# board2.net
KiCad netlist of a schematic drawn in EAGLE
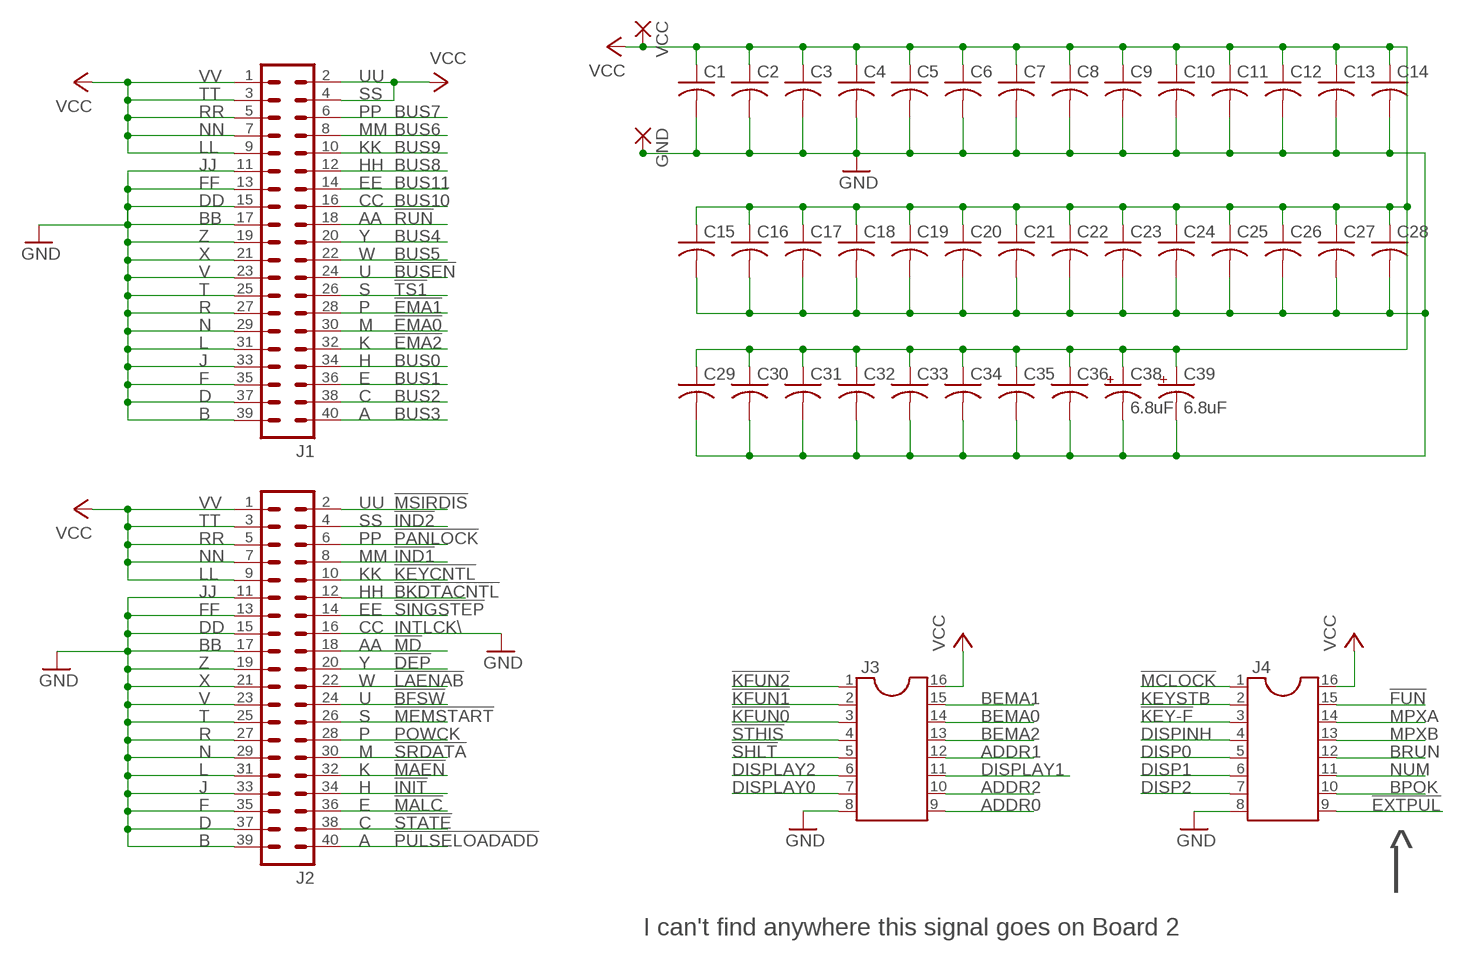
[diagram p0: schematic, sheet 1]
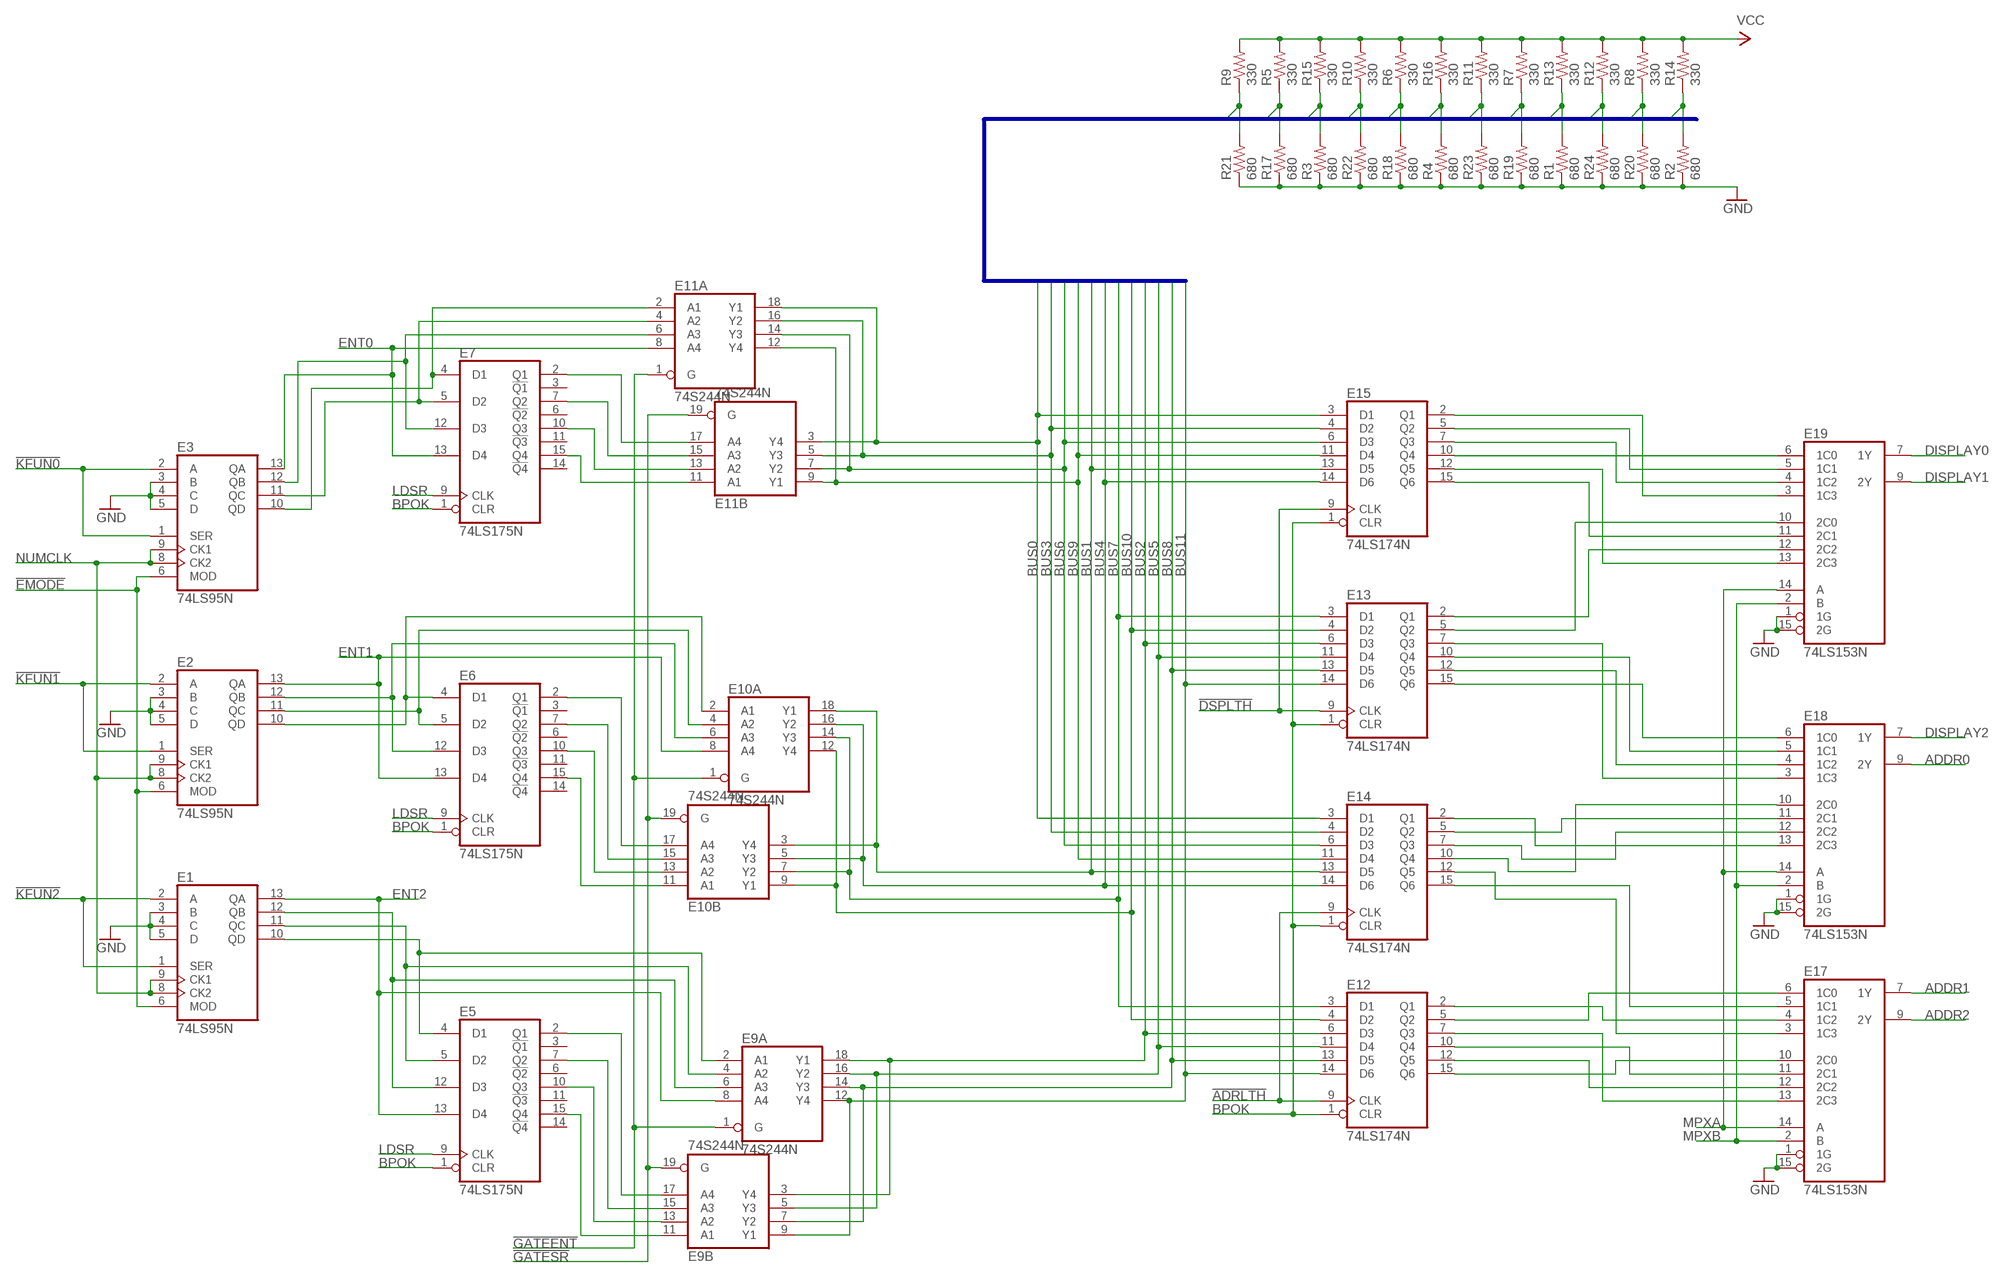
[diagram p1: schematic, sheet 2]
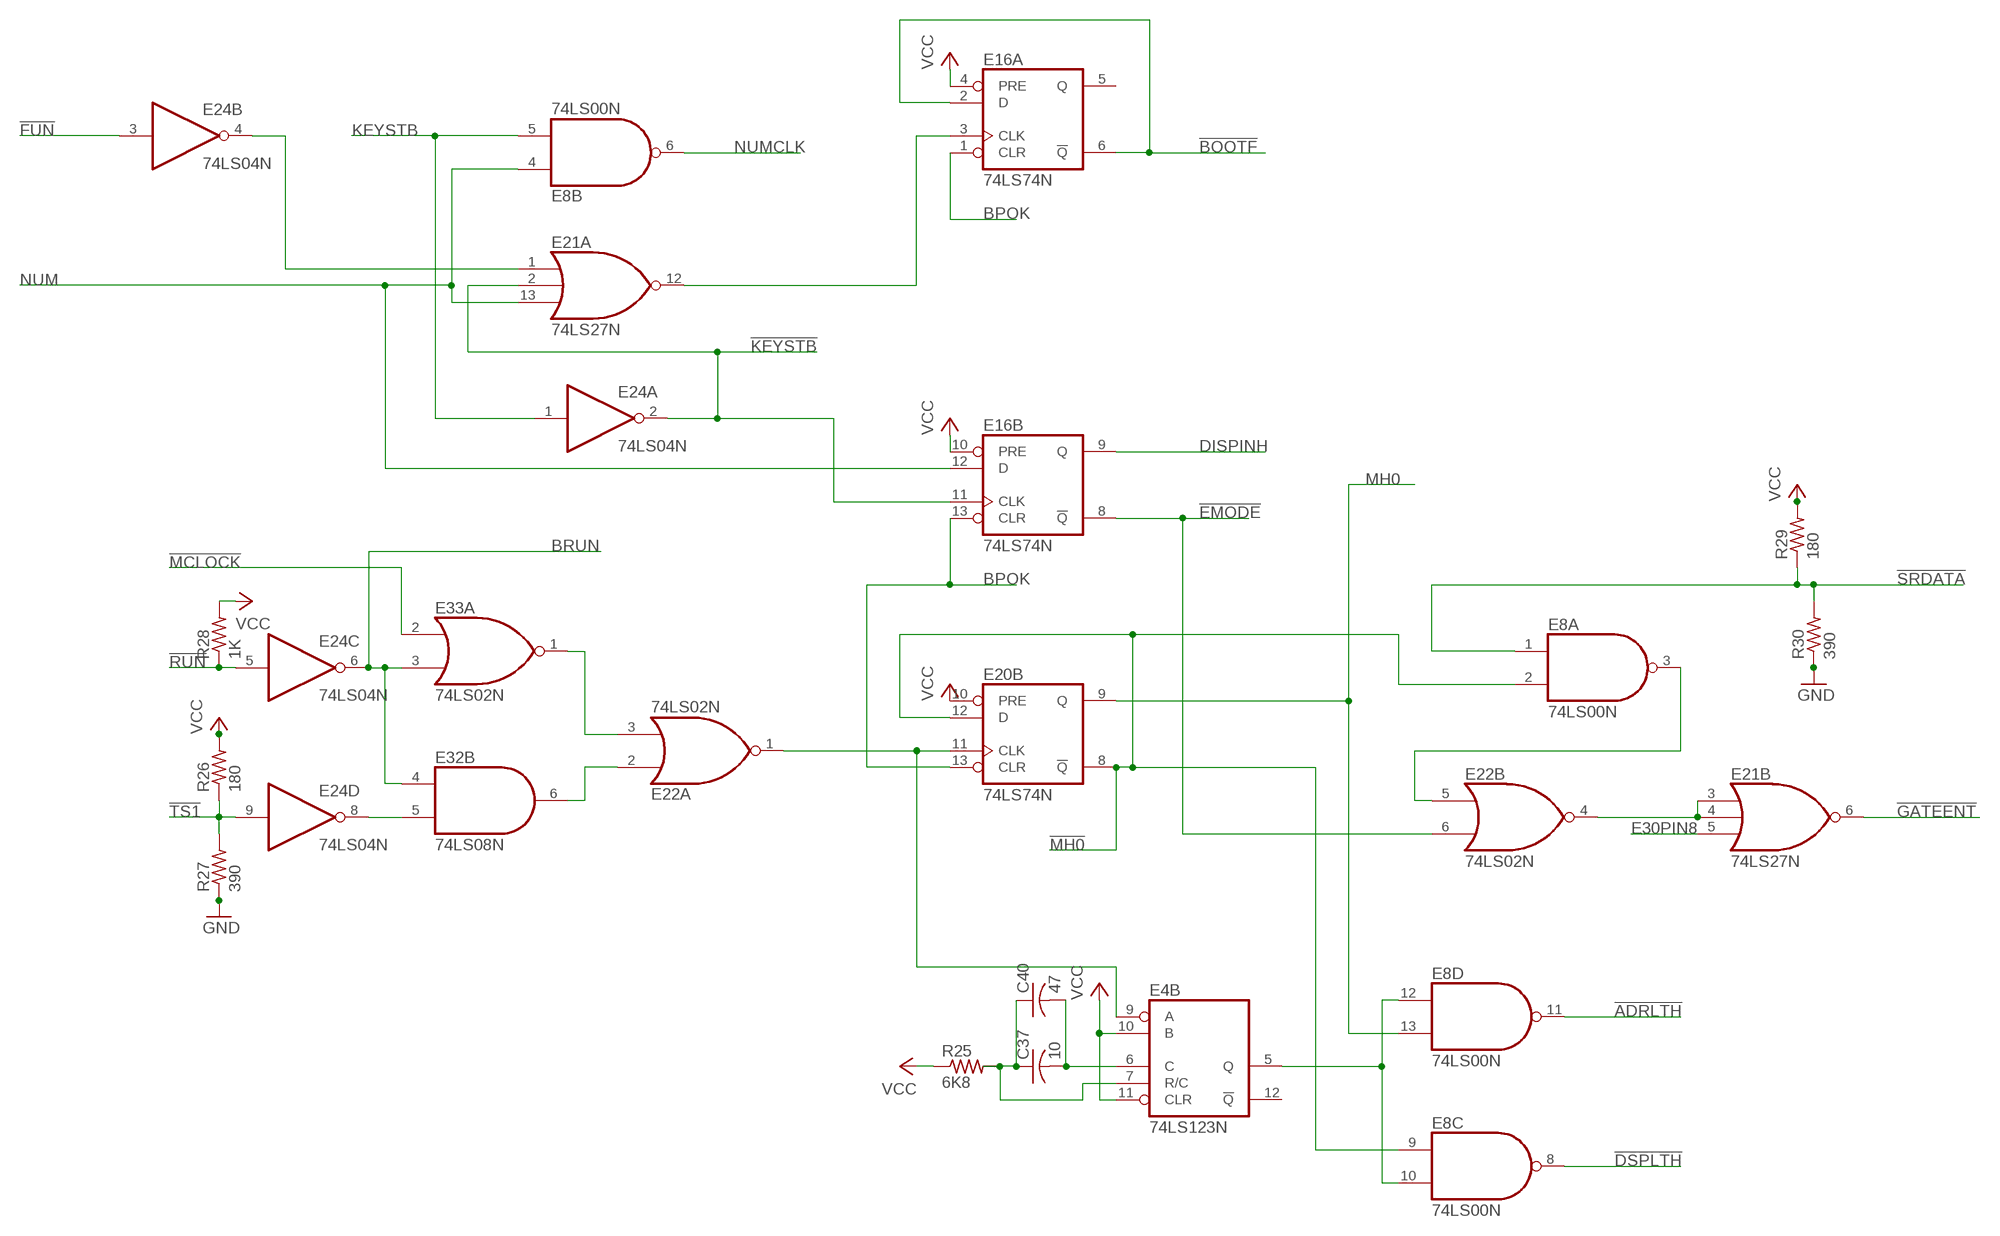
[diagram p2: schematic, sheet 3]
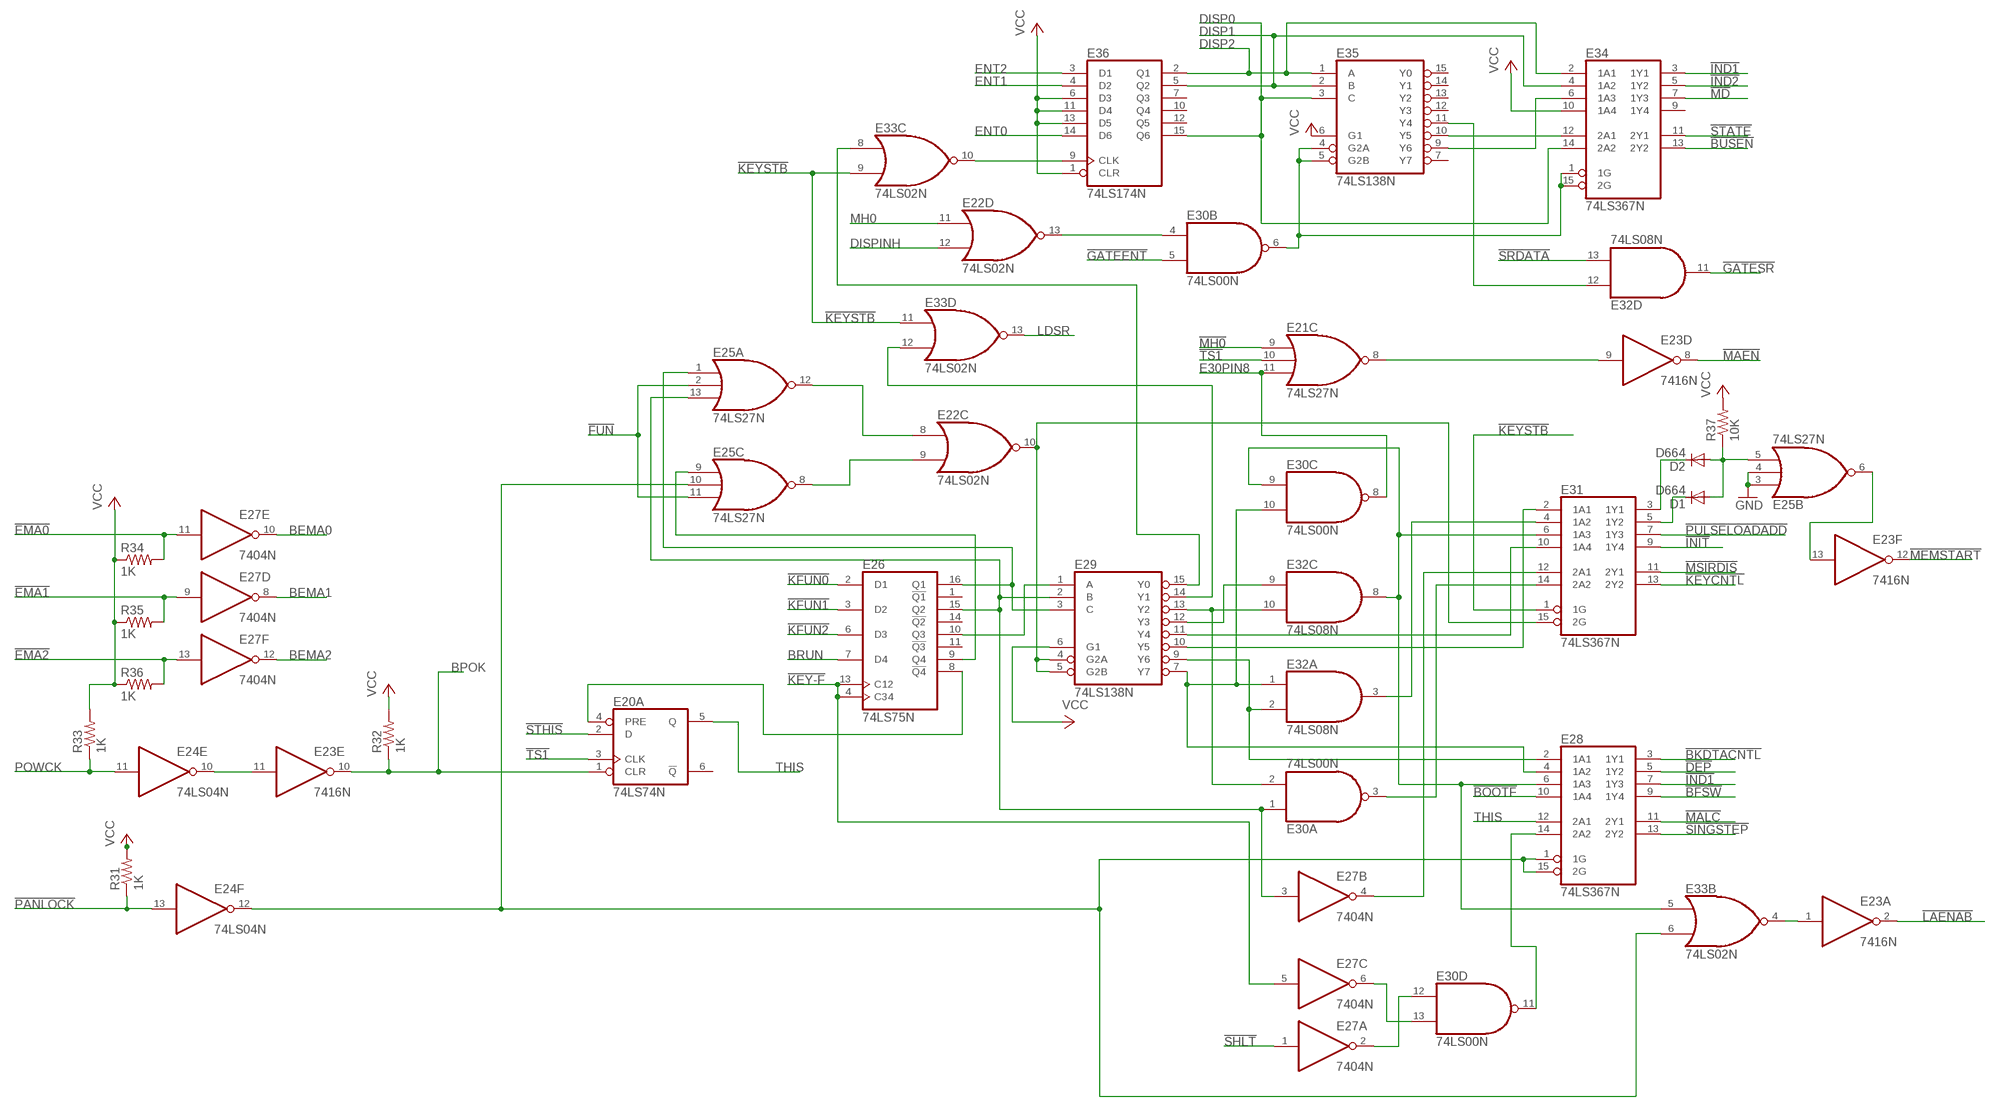
[diagram p3: schematic, sheet 4]

(export (version "E")
  (design (tool "Eeschema 10.0.6"))
  (components
    (comp (ref "C37")
      (value "10")
      (footprint "eagle-import:C050-025X075")
      (libsource (lib "eagle-import") (part "C-US050-025X075"))
    )
    (comp (ref "C40")
      (value "47")
      (footprint "eagle-import:C050-025X075")
      (libsource (lib "eagle-import") (part "C-US050-025X075"))
    )
    (comp (ref "E4")
      (value "74LS123N")
      (footprint "eagle-import:DIL16")
      (libsource (lib "eagle-import") (part "74123NLS"))
    )
    (comp (ref "E8")
      (value "74LS00N")
      (footprint "eagle-import:DIL14")
      (libsource (lib "eagle-import") (part "7400NLS"))
    )
    (comp (ref "E16")
      (value "74LS74N")
      (footprint "eagle-import:DIL14")
      (libsource (lib "eagle-import") (part "7474NLS"))
    )
    (comp (ref "E20")
      (value "74LS74N")
      (footprint "eagle-import:DIL14")
      (libsource (lib "eagle-import") (part "7474NLS"))
    )
    (comp (ref "E21")
      (value "74LS27N")
      (footprint "eagle-import:DIL14")
      (libsource (lib "eagle-import") (part "7427NLS"))
    )
    (comp (ref "E22")
      (value "74LS02N")
      (footprint "eagle-import:DIL14")
      (libsource (lib "eagle-import") (part "7402NLS"))
    )
    (comp (ref "E24")
      (value "74LS04N")
      (footprint "eagle-import:DIL14")
      (libsource (lib "eagle-import") (part "7404NLS"))
    )
    (comp (ref "E32")
      (value "74LS08N")
      (footprint "eagle-import:DIL14")
      (libsource (lib "eagle-import") (part "7408NLS"))
    )
    (comp (ref "E33")
      (value "74LS02N")
      (footprint "eagle-import:DIL14")
      (libsource (lib "eagle-import") (part "7402NLS"))
    )
    (comp (ref "R25")
      (value "6K8")
      (footprint "eagle-import:0207_10")
      (libsource (lib "eagle-import") (part "R-US_0207/10"))
    )
    (comp (ref "R26")
      (value "180")
      (footprint "eagle-import:0207_10")
      (libsource (lib "eagle-import") (part "R-US_0207/10"))
    )
    (comp (ref "R27")
      (value "390")
      (footprint "eagle-import:0207_10")
      (libsource (lib "eagle-import") (part "R-US_0207/10"))
    )
    (comp (ref "R28")
      (value "1K")
      (footprint "eagle-import:0207_10")
      (libsource (lib "eagle-import") (part "R-US_0207/10"))
    )
    (comp (ref "R29")
      (value "180")
      (footprint "eagle-import:0207_10")
      (libsource (lib "eagle-import") (part "R-US_0207/10"))
    )
    (comp (ref "R30")
      (value "390")
      (footprint "eagle-import:0207_10")
      (libsource (lib "eagle-import") (part "R-US_0207/10"))
    )
    (comp (ref "D1")
      (value "D664")
      (footprint "eagle-import:DO35-10")
      (libsource (lib "eagle-import") (part "1N4148DO35-10"))
    )
    (comp (ref "D2")
      (value "D664")
      (footprint "eagle-import:DO35-10")
      (libsource (lib "eagle-import") (part "1N4148DO35-10"))
    )
    (comp (ref "E23")
      (value "7416N")
      (footprint "eagle-import:DIL14")
      (libsource (lib "eagle-import") (part "7416N"))
    )
    (comp (ref "E25")
      (value "74LS27N")
      (footprint "eagle-import:DIL14")
      (libsource (lib "eagle-import") (part "7427NLS"))
    )
    (comp (ref "E26")
      (value "74LS75N")
      (footprint "eagle-import:DIL16")
      (libsource (lib "eagle-import") (part "7475NLS"))
    )
    (comp (ref "E27")
      (value "7404N")
      (footprint "eagle-import:DIL14")
      (libsource (lib "eagle-import") (part "7404N"))
    )
    (comp (ref "E28")
      (value "74LS367N")
      (footprint "eagle-import:DIL16")
      (libsource (lib "eagle-import") (part "74367N"))
    )
    (comp (ref "E29")
      (value "74LS138N")
      (footprint "eagle-import:DIL16")
      (libsource (lib "eagle-import") (part "74138NLS"))
    )
    (comp (ref "E30")
      (value "74LS00N")
      (footprint "eagle-import:DIL14")
      (libsource (lib "eagle-import") (part "7400NLS"))
    )
    (comp (ref "E31")
      (value "74LS367N")
      (footprint "eagle-import:DIL16")
      (libsource (lib "eagle-import") (part "74367N"))
    )
    (comp (ref "E34")
      (value "74LS367N")
      (footprint "eagle-import:DIL16")
      (libsource (lib "eagle-import") (part "74367N"))
    )
    (comp (ref "E35")
      (value "74LS138N")
      (footprint "eagle-import:DIL16")
      (libsource (lib "eagle-import") (part "74138NLS"))
    )
    (comp (ref "E36")
      (value "74LS174N")
      (footprint "eagle-import:DIL16")
      (libsource (lib "eagle-import") (part "74174NLS"))
    )
    (comp (ref "R31")
      (value "1K")
      (footprint "eagle-import:0207_10")
      (libsource (lib "eagle-import") (part "R-US_0207/10"))
    )
    (comp (ref "R32")
      (value "1K")
      (footprint "eagle-import:0207_10")
      (libsource (lib "eagle-import") (part "R-US_0207/10"))
    )
    (comp (ref "R33")
      (value "1K")
      (footprint "eagle-import:0207_10")
      (libsource (lib "eagle-import") (part "R-US_0207/10"))
    )
    (comp (ref "R34")
      (value "1K")
      (footprint "eagle-import:0207_10")
      (libsource (lib "eagle-import") (part "R-US_0207/10"))
    )
    (comp (ref "R35")
      (value "1K")
      (footprint "eagle-import:0207_10")
      (libsource (lib "eagle-import") (part "R-US_0207/10"))
    )
    (comp (ref "R36")
      (value "1K")
      (footprint "eagle-import:0207_10")
      (libsource (lib "eagle-import") (part "R-US_0207/10"))
    )
    (comp (ref "R37")
      (value "10K")
      (footprint "eagle-import:0207_10")
      (libsource (lib "eagle-import") (part "R-US_0207/10"))
    )
    (comp (ref "C1")
      (value "C-US050-025X075")
      (footprint "eagle-import:C050-025X075")
      (libsource (lib "eagle-import") (part "C-US050-025X075"))
    )
    (comp (ref "C2")
      (value "C-US050-025X075")
      (footprint "eagle-import:C050-025X075")
      (libsource (lib "eagle-import") (part "C-US050-025X075"))
    )
    (comp (ref "C3")
      (value "C-US050-025X075")
      (footprint "eagle-import:C050-025X075")
      (libsource (lib "eagle-import") (part "C-US050-025X075"))
    )
    (comp (ref "C4")
      (value "C-US050-025X075")
      (footprint "eagle-import:C050-025X075")
      (libsource (lib "eagle-import") (part "C-US050-025X075"))
    )
    (comp (ref "C5")
      (value "C-US050-025X075")
      (footprint "eagle-import:C050-025X075")
      (libsource (lib "eagle-import") (part "C-US050-025X075"))
    )
    (comp (ref "C6")
      (value "C-US050-025X075")
      (footprint "eagle-import:C050-025X075")
      (libsource (lib "eagle-import") (part "C-US050-025X075"))
    )
    (comp (ref "C7")
      (value "C-US050-025X075")
      (footprint "eagle-import:C050-025X075")
      (libsource (lib "eagle-import") (part "C-US050-025X075"))
    )
    (comp (ref "C8")
      (value "C-US050-025X075")
      (footprint "eagle-import:C050-025X075")
      (libsource (lib "eagle-import") (part "C-US050-025X075"))
    )
    (comp (ref "C9")
      (value "C-US050-025X075")
      (footprint "eagle-import:C050-025X075")
      (libsource (lib "eagle-import") (part "C-US050-025X075"))
    )
    (comp (ref "C10")
      (value "C-US050-025X075")
      (footprint "eagle-import:C050-025X075")
      (libsource (lib "eagle-import") (part "C-US050-025X075"))
    )
    (comp (ref "C11")
      (value "C-US050-025X075")
      (footprint "eagle-import:C050-025X075")
      (libsource (lib "eagle-import") (part "C-US050-025X075"))
    )
    (comp (ref "C12")
      (value "C-US050-025X075")
      (footprint "eagle-import:C050-025X075")
      (libsource (lib "eagle-import") (part "C-US050-025X075"))
    )
    (comp (ref "C13")
      (value "C-US050-025X075")
      (footprint "eagle-import:C050-025X075")
      (libsource (lib "eagle-import") (part "C-US050-025X075"))
    )
    (comp (ref "C14")
      (value "C-US050-025X075")
      (footprint "eagle-import:C050-025X075")
      (libsource (lib "eagle-import") (part "C-US050-025X075"))
    )
    (comp (ref "C15")
      (value "C-US050-025X075")
      (footprint "eagle-import:C050-025X075")
      (libsource (lib "eagle-import") (part "C-US050-025X075"))
    )
    (comp (ref "C16")
      (value "C-US050-025X075")
      (footprint "eagle-import:C050-025X075")
      (libsource (lib "eagle-import") (part "C-US050-025X075"))
    )
    (comp (ref "C17")
      (value "C-US050-025X075")
      (footprint "eagle-import:C050-025X075")
      (libsource (lib "eagle-import") (part "C-US050-025X075"))
    )
    (comp (ref "C18")
      (value "C-US050-025X075")
      (footprint "eagle-import:C050-025X075")
      (libsource (lib "eagle-import") (part "C-US050-025X075"))
    )
    (comp (ref "C19")
      (value "C-US050-025X075")
      (footprint "eagle-import:C050-025X075")
      (libsource (lib "eagle-import") (part "C-US050-025X075"))
    )
    (comp (ref "C20")
      (value "C-US050-025X075")
      (footprint "eagle-import:C050-025X075")
      (libsource (lib "eagle-import") (part "C-US050-025X075"))
    )
    (comp (ref "C21")
      (value "C-US050-025X075")
      (footprint "eagle-import:C050-025X075")
      (libsource (lib "eagle-import") (part "C-US050-025X075"))
    )
    (comp (ref "C22")
      (value "C-US050-025X075")
      (footprint "eagle-import:C050-025X075")
      (libsource (lib "eagle-import") (part "C-US050-025X075"))
    )
    (comp (ref "C23")
      (value "C-US050-025X075")
      (footprint "eagle-import:C050-025X075")
      (libsource (lib "eagle-import") (part "C-US050-025X075"))
    )
    (comp (ref "C24")
      (value "C-US050-025X075")
      (footprint "eagle-import:C050-025X075")
      (libsource (lib "eagle-import") (part "C-US050-025X075"))
    )
    (comp (ref "C25")
      (value "C-US050-025X075")
      (footprint "eagle-import:C050-025X075")
      (libsource (lib "eagle-import") (part "C-US050-025X075"))
    )
    (comp (ref "C26")
      (value "C-US050-025X075")
      (footprint "eagle-import:C050-025X075")
      (libsource (lib "eagle-import") (part "C-US050-025X075"))
    )
    (comp (ref "C27")
      (value "C-US050-025X075")
      (footprint "eagle-import:C050-025X075")
      (libsource (lib "eagle-import") (part "C-US050-025X075"))
    )
    (comp (ref "C28")
      (value "C-US050-025X075")
      (footprint "eagle-import:C050-025X075")
      (libsource (lib "eagle-import") (part "C-US050-025X075"))
    )
    (comp (ref "C29")
      (value "C-US050-025X075")
      (footprint "eagle-import:C050-025X075")
      (libsource (lib "eagle-import") (part "C-US050-025X075"))
    )
    (comp (ref "C30")
      (value "C-US050-025X075")
      (footprint "eagle-import:C050-025X075")
      (libsource (lib "eagle-import") (part "C-US050-025X075"))
    )
    (comp (ref "C31")
      (value "C-US050-025X075")
      (footprint "eagle-import:C050-025X075")
      (libsource (lib "eagle-import") (part "C-US050-025X075"))
    )
    (comp (ref "C32")
      (value "C-US050-025X075")
      (footprint "eagle-import:C050-025X075")
      (libsource (lib "eagle-import") (part "C-US050-025X075"))
    )
    (comp (ref "C33")
      (value "C-US050-025X075")
      (footprint "eagle-import:C050-025X075")
      (libsource (lib "eagle-import") (part "C-US050-025X075"))
    )
    (comp (ref "C34")
      (value "C-US050-025X075")
      (footprint "eagle-import:C050-025X075")
      (libsource (lib "eagle-import") (part "C-US050-025X075"))
    )
    (comp (ref "C35")
      (value "C-US050-025X075")
      (footprint "eagle-import:C050-025X075")
      (libsource (lib "eagle-import") (part "C-US050-025X075"))
    )
    (comp (ref "C36")
      (value "C-US050-025X075")
      (footprint "eagle-import:C050-025X075")
      (libsource (lib "eagle-import") (part "C-US050-025X075"))
    )
    (comp (ref "C38")
      (value "6.8uF")
      (footprint "eagle-import:E15-5")
      (libsource (lib "eagle-import") (part "CPOL-USE15-5AXIAL"))
    )
    (comp (ref "C39")
      (value "6.8uF")
      (footprint "eagle-import:E15-5")
      (libsource (lib "eagle-import") (part "CPOL-USE15-5AXIAL"))
    )
    (comp (ref "GND")
      (value "3,81/1,4")
      (footprint "eagle-import:3,81_1,4")
      (libsource (lib "eagle-import") (part "3,81/1,4"))
    )
    (comp (ref "J1")
      (value "40H")
      (footprint "eagle-import:40H")
      (libsource (lib "eagle-import") (part "40H"))
    )
    (comp (ref "J2")
      (value "40H")
      (footprint "eagle-import:40H")
      (libsource (lib "eagle-import") (part "40H"))
    )
    (comp (ref "J3")
      (value "DIL16S")
      (footprint "eagle-import:SOCKET-16")
      (libsource (lib "eagle-import") (part "DIL16S"))
    )
    (comp (ref "J4")
      (value "DIL16S")
      (footprint "eagle-import:SOCKET-16")
      (libsource (lib "eagle-import") (part "DIL16S"))
    )
    (comp (ref "VCC")
      (value "3,81/1,4")
      (footprint "eagle-import:3,81_1,4")
      (libsource (lib "eagle-import") (part "3,81/1,4"))
    )
    (comp (ref "E1")
      (value "74LS95N")
      (footprint "eagle-import:DIL14")
      (libsource (lib "eagle-import") (part "7495NLS"))
    )
    (comp (ref "E2")
      (value "74LS95N")
      (footprint "eagle-import:DIL14")
      (libsource (lib "eagle-import") (part "7495NLS"))
    )
    (comp (ref "E3")
      (value "74LS95N")
      (footprint "eagle-import:DIL14")
      (libsource (lib "eagle-import") (part "7495NLS"))
    )
    (comp (ref "E5")
      (value "74LS175N")
      (footprint "eagle-import:DIL16")
      (libsource (lib "eagle-import") (part "74175NLS"))
    )
    (comp (ref "E6")
      (value "74LS175N")
      (footprint "eagle-import:DIL16")
      (libsource (lib "eagle-import") (part "74175NLS"))
    )
    (comp (ref "E7")
      (value "74LS175N")
      (footprint "eagle-import:DIL16")
      (libsource (lib "eagle-import") (part "74175NLS"))
    )
    (comp (ref "E9")
      (value "74S244N")
      (footprint "eagle-import:DIL20")
      (libsource (lib "eagle-import") (part "74244NS"))
    )
    (comp (ref "E10")
      (value "74S244N")
      (footprint "eagle-import:DIL20")
      (libsource (lib "eagle-import") (part "74244NS"))
    )
    (comp (ref "E11")
      (value "74S244N")
      (footprint "eagle-import:DIL20")
      (libsource (lib "eagle-import") (part "74244NS"))
    )
    (comp (ref "E12")
      (value "74LS174N")
      (footprint "eagle-import:DIL16")
      (libsource (lib "eagle-import") (part "74174NLS"))
    )
    (comp (ref "E13")
      (value "74LS174N")
      (footprint "eagle-import:DIL16")
      (libsource (lib "eagle-import") (part "74174NLS"))
    )
    (comp (ref "E14")
      (value "74LS174N")
      (footprint "eagle-import:DIL16")
      (libsource (lib "eagle-import") (part "74174NLS"))
    )
    (comp (ref "E15")
      (value "74LS174N")
      (footprint "eagle-import:DIL16")
      (libsource (lib "eagle-import") (part "74174NLS"))
    )
    (comp (ref "E17")
      (value "74LS153N")
      (footprint "eagle-import:DIL16")
      (libsource (lib "eagle-import") (part "74153NLS"))
    )
    (comp (ref "E18")
      (value "74LS153N")
      (footprint "eagle-import:DIL16")
      (libsource (lib "eagle-import") (part "74153NLS"))
    )
    (comp (ref "E19")
      (value "74LS153N")
      (footprint "eagle-import:DIL16")
      (libsource (lib "eagle-import") (part "74153NLS"))
    )
    (comp (ref "R1")
      (value "680")
      (footprint "eagle-import:0207_10")
      (libsource (lib "eagle-import") (part "R-US_0207/10"))
    )
    (comp (ref "R2")
      (value "680")
      (footprint "eagle-import:0207_10")
      (libsource (lib "eagle-import") (part "R-US_0207/10"))
    )
    (comp (ref "R3")
      (value "680")
      (footprint "eagle-import:0207_10")
      (libsource (lib "eagle-import") (part "R-US_0207/10"))
    )
    (comp (ref "R4")
      (value "680")
      (footprint "eagle-import:0207_10")
      (libsource (lib "eagle-import") (part "R-US_0207/10"))
    )
    (comp (ref "R5")
      (value "330")
      (footprint "eagle-import:0207_10")
      (libsource (lib "eagle-import") (part "R-US_0207/10"))
    )
    (comp (ref "R6")
      (value "330")
      (footprint "eagle-import:0207_10")
      (libsource (lib "eagle-import") (part "R-US_0207/10"))
    )
    (comp (ref "R7")
      (value "330")
      (footprint "eagle-import:0207_10")
      (libsource (lib "eagle-import") (part "R-US_0207/10"))
    )
    (comp (ref "R8")
      (value "330")
      (footprint "eagle-import:0207_10")
      (libsource (lib "eagle-import") (part "R-US_0207/10"))
    )
    (comp (ref "R9")
      (value "330")
      (footprint "eagle-import:0207_10")
      (libsource (lib "eagle-import") (part "R-US_0207/10"))
    )
    (comp (ref "R10")
      (value "330")
      (footprint "eagle-import:0207_10")
      (libsource (lib "eagle-import") (part "R-US_0207/10"))
    )
    (comp (ref "R11")
      (value "330")
      (footprint "eagle-import:0207_10")
      (libsource (lib "eagle-import") (part "R-US_0207/10"))
    )
    (comp (ref "R12")
      (value "330")
      (footprint "eagle-import:0207_10")
      (libsource (lib "eagle-import") (part "R-US_0207/10"))
    )
    (comp (ref "R13")
      (value "330")
      (footprint "eagle-import:0207_10")
      (libsource (lib "eagle-import") (part "R-US_0207/10"))
    )
    (comp (ref "R14")
      (value "330")
      (footprint "eagle-import:0207_10")
      (libsource (lib "eagle-import") (part "R-US_0207/10"))
    )
    (comp (ref "R15")
      (value "330")
      (footprint "eagle-import:0207_10")
      (libsource (lib "eagle-import") (part "R-US_0207/10"))
    )
    (comp (ref "R16")
      (value "330")
      (footprint "eagle-import:0207_10")
      (libsource (lib "eagle-import") (part "R-US_0207/10"))
    )
    (comp (ref "R17")
      (value "680")
      (footprint "eagle-import:0207_10")
      (libsource (lib "eagle-import") (part "R-US_0207/10"))
    )
    (comp (ref "R18")
      (value "680")
      (footprint "eagle-import:0207_10")
      (libsource (lib "eagle-import") (part "R-US_0207/10"))
    )
    (comp (ref "R19")
      (value "680")
      (footprint "eagle-import:0207_10")
      (libsource (lib "eagle-import") (part "R-US_0207/10"))
    )
    (comp (ref "R20")
      (value "680")
      (footprint "eagle-import:0207_10")
      (libsource (lib "eagle-import") (part "R-US_0207/10"))
    )
    (comp (ref "R21")
      (value "680")
      (footprint "eagle-import:0207_10")
      (libsource (lib "eagle-import") (part "R-US_0207/10"))
    )
    (comp (ref "R22")
      (value "680")
      (footprint "eagle-import:0207_10")
      (libsource (lib "eagle-import") (part "R-US_0207/10"))
    )
    (comp (ref "R23")
      (value "680")
      (footprint "eagle-import:0207_10")
      (libsource (lib "eagle-import") (part "R-US_0207/10"))
    )
    (comp (ref "R24")
      (value "680")
      (footprint "eagle-import:0207_10")
      (libsource (lib "eagle-import") (part "R-US_0207/10"))
    )
  )
  (nets
    (net (code "1") (name "ADDR0") (class "Default")
      (node (ref "E18") (pin "9") (pinfunction "2Y_9") (pintype "output"))
      (node (ref "J3") (pin "9") (pinfunction "9_9") (pintype "passive"))
    )
    (net (code "2") (name "ADDR1") (class "Default")
      (node (ref "E17") (pin "7") (pinfunction "1Y_7") (pintype "output"))
      (node (ref "J3") (pin "12") (pinfunction "12_12") (pintype "passive"))
    )
    (net (code "3") (name "ADDR2") (class "Default")
      (node (ref "E17") (pin "9") (pinfunction "2Y_9") (pintype "output"))
      (node (ref "J3") (pin "10") (pinfunction "10_10") (pintype "passive"))
    )
    (net (code "4") (name "BEMA0") (class "Default")
      (node (ref "E27") (pin "10") (pinfunction "O_10") (pintype "output"))
      (node (ref "J3") (pin "14") (pinfunction "14_14") (pintype "passive"))
    )
    (net (code "5") (name "BEMA1") (class "Default")
      (node (ref "E27") (pin "8") (pinfunction "O_8") (pintype "output"))
      (node (ref "J3") (pin "15") (pinfunction "15_15") (pintype "passive"))
    )
    (net (code "6") (name "BEMA2") (class "Default")
      (node (ref "E27") (pin "12") (pinfunction "O_12") (pintype "output"))
      (node (ref "J3") (pin "13") (pinfunction "13_13") (pintype "passive"))
    )
    (net (code "7") (name "BPOK") (class "Default")
      (node (ref "E12") (pin "1") (pinfunction "CLR_1") (pintype "input"))
      (node (ref "E13") (pin "1") (pinfunction "CLR_1") (pintype "input"))
      (node (ref "E14") (pin "1") (pinfunction "CLR_1") (pintype "input"))
      (node (ref "E15") (pin "1") (pinfunction "CLR_1") (pintype "input"))
      (node (ref "E16") (pin "1") (pinfunction "CLR_1") (pintype "input"))
      (node (ref "E16") (pin "13") (pinfunction "CLR_13") (pintype "input"))
      (node (ref "E20") (pin "1") (pinfunction "CLR_1") (pintype "input"))
      (node (ref "E20") (pin "13") (pinfunction "CLR_13") (pintype "input"))
      (node (ref "E23") (pin "10") (pinfunction "O_10") (pintype "open_collector"))
      (node (ref "E5") (pin "1") (pinfunction "CLR_1") (pintype "input"))
      (node (ref "E6") (pin "1") (pinfunction "CLR_1") (pintype "input"))
      (node (ref "E7") (pin "1") (pinfunction "CLR_1") (pintype "input"))
      (node (ref "J4") (pin "10") (pinfunction "10_10") (pintype "passive"))
      (node (ref "R32") (pin "1") (pinfunction "1_1") (pintype "passive"))
    )
    (net (code "8") (name "BRUN") (class "Default")
      (node (ref "E24") (pin "6") (pinfunction "O_6") (pintype "output"))
      (node (ref "E26") (pin "7") (pinfunction "D4_7") (pintype "input"))
      (node (ref "E32") (pin "4") (pinfunction "I0_4") (pintype "input"))
      (node (ref "E33") (pin "3") (pinfunction "I1_3") (pintype "input"))
      (node (ref "J4") (pin "12") (pinfunction "12_12") (pintype "passive"))
    )
    (net (code "9") (name "BUS0") (class "Default")
      (node (ref "E11") (pin "18") (pinfunction "Y1_18") (pintype "tri_state"))
      (node (ref "E11") (pin "3") (pinfunction "Y4_3") (pintype "tri_state"))
      (node (ref "E14") (pin "3") (pinfunction "D1_3") (pintype "input"))
      (node (ref "E15") (pin "3") (pinfunction "D1_3") (pintype "input"))
      (node (ref "J1") (pin "34") (pinfunction "34_34") (pintype "passive"))
      (node (ref "R21") (pin "2") (pinfunction "2_2") (pintype "passive"))
      (node (ref "R9") (pin "1") (pinfunction "1_1") (pintype "passive"))
    )
    (net (code "10") (name "BUS1") (class "Default")
      (node (ref "E10") (pin "18") (pinfunction "Y1_18") (pintype "tri_state"))
      (node (ref "E10") (pin "3") (pinfunction "Y4_3") (pintype "tri_state"))
      (node (ref "E14") (pin "13") (pinfunction "D5_13") (pintype "input"))
      (node (ref "E15") (pin "13") (pinfunction "D5_13") (pintype "input"))
      (node (ref "J1") (pin "36") (pinfunction "36_36") (pintype "passive"))
      (node (ref "R17") (pin "2") (pinfunction "2_2") (pintype "passive"))
      (node (ref "R5") (pin "1") (pinfunction "1_1") (pintype "passive"))
    )
    (net (code "11") (name "BUS2") (class "Default")
      (node (ref "E12") (pin "6") (pinfunction "D3_6") (pintype "input"))
      (node (ref "E13") (pin "6") (pinfunction "D3_6") (pintype "input"))
      (node (ref "E9") (pin "18") (pinfunction "Y1_18") (pintype "tri_state"))
      (node (ref "E9") (pin "3") (pinfunction "Y4_3") (pintype "tri_state"))
      (node (ref "J1") (pin "38") (pinfunction "38_38") (pintype "passive"))
      (node (ref "R15") (pin "1") (pinfunction "1_1") (pintype "passive"))
      (node (ref "R3") (pin "2") (pinfunction "2_2") (pintype "passive"))
    )
    (net (code "12") (name "BUS3") (class "Default")
      (node (ref "E11") (pin "16") (pinfunction "Y2_16") (pintype "tri_state"))
      (node (ref "E11") (pin "5") (pinfunction "Y3_5") (pintype "tri_state"))
      (node (ref "E14") (pin "4") (pinfunction "D2_4") (pintype "input"))
      (node (ref "E15") (pin "4") (pinfunction "D2_4") (pintype "input"))
      (node (ref "J1") (pin "40") (pinfunction "40_40") (pintype "passive"))
      (node (ref "R10") (pin "1") (pinfunction "1_1") (pintype "passive"))
      (node (ref "R22") (pin "2") (pinfunction "2_2") (pintype "passive"))
    )
    (net (code "13") (name "BUS4") (class "Default")
      (node (ref "E10") (pin "16") (pinfunction "Y2_16") (pintype "tri_state"))
      (node (ref "E10") (pin "5") (pinfunction "Y3_5") (pintype "tri_state"))
      (node (ref "E14") (pin "14") (pinfunction "D6_14") (pintype "input"))
      (node (ref "E15") (pin "14") (pinfunction "D6_14") (pintype "input"))
      (node (ref "J1") (pin "20") (pinfunction "20_20") (pintype "passive"))
      (node (ref "R18") (pin "2") (pinfunction "2_2") (pintype "passive"))
      (node (ref "R6") (pin "1") (pinfunction "1_1") (pintype "passive"))
    )
    (net (code "14") (name "BUS5") (class "Default")
      (node (ref "E12") (pin "11") (pinfunction "D4_11") (pintype "input"))
      (node (ref "E13") (pin "11") (pinfunction "D4_11") (pintype "input"))
      (node (ref "E9") (pin "16") (pinfunction "Y2_16") (pintype "tri_state"))
      (node (ref "E9") (pin "5") (pinfunction "Y3_5") (pintype "tri_state"))
      (node (ref "J1") (pin "22") (pinfunction "22_22") (pintype "passive"))
      (node (ref "R16") (pin "1") (pinfunction "1_1") (pintype "passive"))
      (node (ref "R4") (pin "2") (pinfunction "2_2") (pintype "passive"))
    )
    (net (code "15") (name "BUS6") (class "Default")
      (node (ref "E11") (pin "14") (pinfunction "Y3_14") (pintype "tri_state"))
      (node (ref "E11") (pin "7") (pinfunction "Y2_7") (pintype "tri_state"))
      (node (ref "E14") (pin "6") (pinfunction "D3_6") (pintype "input"))
      (node (ref "E15") (pin "6") (pinfunction "D3_6") (pintype "input"))
      (node (ref "J1") (pin "8") (pinfunction "8_8") (pintype "passive"))
      (node (ref "R11") (pin "1") (pinfunction "1_1") (pintype "passive"))
      (node (ref "R23") (pin "2") (pinfunction "2_2") (pintype "passive"))
    )
    (net (code "16") (name "BUS7") (class "Default")
      (node (ref "E10") (pin "14") (pinfunction "Y3_14") (pintype "tri_state"))
      (node (ref "E10") (pin "7") (pinfunction "Y2_7") (pintype "tri_state"))
      (node (ref "E12") (pin "3") (pinfunction "D1_3") (pintype "input"))
      (node (ref "E13") (pin "3") (pinfunction "D1_3") (pintype "input"))
      (node (ref "J1") (pin "6") (pinfunction "6_6") (pintype "passive"))
      (node (ref "R19") (pin "2") (pinfunction "2_2") (pintype "passive"))
      (node (ref "R7") (pin "1") (pinfunction "1_1") (pintype "passive"))
    )
    (net (code "17") (name "BUS8") (class "Default")
      (node (ref "E12") (pin "13") (pinfunction "D5_13") (pintype "input"))
      (node (ref "E13") (pin "13") (pinfunction "D5_13") (pintype "input"))
      (node (ref "E9") (pin "14") (pinfunction "Y3_14") (pintype "tri_state"))
      (node (ref "E9") (pin "7") (pinfunction "Y2_7") (pintype "tri_state"))
      (node (ref "J1") (pin "12") (pinfunction "12_12") (pintype "passive"))
      (node (ref "R1") (pin "2") (pinfunction "2_2") (pintype "passive"))
      (node (ref "R13") (pin "1") (pinfunction "1_1") (pintype "passive"))
    )
    (net (code "18") (name "BUS9") (class "Default")
      (node (ref "E11") (pin "12") (pinfunction "Y4_12") (pintype "tri_state"))
      (node (ref "E11") (pin "9") (pinfunction "Y1_9") (pintype "tri_state"))
      (node (ref "E14") (pin "11") (pinfunction "D4_11") (pintype "input"))
      (node (ref "E15") (pin "11") (pinfunction "D4_11") (pintype "input"))
      (node (ref "J1") (pin "10") (pinfunction "10_10") (pintype "passive"))
      (node (ref "R12") (pin "1") (pinfunction "1_1") (pintype "passive"))
      (node (ref "R24") (pin "2") (pinfunction "2_2") (pintype "passive"))
    )
    (net (code "19") (name "BUS10") (class "Default")
      (node (ref "E10") (pin "12") (pinfunction "Y4_12") (pintype "tri_state"))
      (node (ref "E10") (pin "9") (pinfunction "Y1_9") (pintype "tri_state"))
      (node (ref "E12") (pin "4") (pinfunction "D2_4") (pintype "input"))
      (node (ref "E13") (pin "4") (pinfunction "D2_4") (pintype "input"))
      (node (ref "J1") (pin "16") (pinfunction "16_16") (pintype "passive"))
      (node (ref "R20") (pin "2") (pinfunction "2_2") (pintype "passive"))
      (node (ref "R8") (pin "1") (pinfunction "1_1") (pintype "passive"))
    )
    (net (code "20") (name "BUS11") (class "Default")
      (node (ref "E12") (pin "14") (pinfunction "D6_14") (pintype "input"))
      (node (ref "E13") (pin "14") (pinfunction "D6_14") (pintype "input"))
      (node (ref "E9") (pin "12") (pinfunction "Y4_12") (pintype "tri_state"))
      (node (ref "E9") (pin "9") (pinfunction "Y1_9") (pintype "tri_state"))
      (node (ref "J1") (pin "14") (pinfunction "14_14") (pintype "passive"))
      (node (ref "R14") (pin "1") (pinfunction "1_1") (pintype "passive"))
      (node (ref "R2") (pin "2") (pinfunction "2_2") (pintype "passive"))
    )
    (net (code "21") (name "DISP0") (class "Default")
      (node (ref "E34") (pin "14") (pinfunction "2A2_14") (pintype "input"))
      (node (ref "E35") (pin "3") (pinfunction "C_3") (pintype "input"))
      (node (ref "E36") (pin "15") (pinfunction "Q6_15") (pintype "output"))
      (node (ref "J4") (pin "5") (pinfunction "5_5") (pintype "passive"))
    )
    (net (code "22") (name "DISP1") (class "Default")
      (node (ref "E34") (pin "4") (pinfunction "1A2_4") (pintype "input"))
      (node (ref "E35") (pin "2") (pinfunction "B_2") (pintype "input"))
      (node (ref "E36") (pin "5") (pinfunction "Q2_5") (pintype "output"))
      (node (ref "J4") (pin "6") (pinfunction "6_6") (pintype "passive"))
    )
    (net (code "23") (name "DISP2") (class "Default")
      (node (ref "E34") (pin "2") (pinfunction "1A1_2") (pintype "input"))
      (node (ref "E35") (pin "1") (pinfunction "A_1") (pintype "input"))
      (node (ref "E36") (pin "2") (pinfunction "Q1_2") (pintype "output"))
      (node (ref "J4") (pin "7") (pinfunction "7_7") (pintype "passive"))
    )
    (net (code "24") (name "DISPINH") (class "Default")
      (node (ref "E16") (pin "9") (pinfunction "Q_9") (pintype "output"))
      (node (ref "E22") (pin "12") (pinfunction "I1_12") (pintype "input"))
      (node (ref "J4") (pin "4") (pinfunction "4_4") (pintype "passive"))
    )
    (net (code "25") (name "DISPLAY0") (class "Default")
      (node (ref "E19") (pin "7") (pinfunction "1Y_7") (pintype "output"))
      (node (ref "J3") (pin "7") (pinfunction "7_7") (pintype "passive"))
    )
    (net (code "26") (name "DISPLAY1") (class "Default")
      (node (ref "E19") (pin "9") (pinfunction "2Y_9") (pintype "output"))
      (node (ref "J3") (pin "11") (pinfunction "11_11") (pintype "passive"))
    )
    (net (code "27") (name "DISPLAY2") (class "Default")
      (node (ref "E18") (pin "7") (pinfunction "1Y_7") (pintype "output"))
      (node (ref "J3") (pin "6") (pinfunction "6_6") (pintype "passive"))
    )
    (net (code "28") (name "E30PIN8") (class "Default")
      (node (ref "E21") (pin "11") (pinfunction "I2_11") (pintype "input"))
      (node (ref "E21") (pin "5") (pinfunction "I2_5") (pintype "input"))
      (node (ref "E30") (pin "8") (pinfunction "O_8") (pintype "output"))
    )
    (net (code "29") (name "ENT0") (class "Default")
      (node (ref "E11") (pin "8") (pinfunction "A4_8") (pintype "input"))
      (node (ref "E3") (pin "13") (pinfunction "QA_13") (pintype "output"))
      (node (ref "E36") (pin "14") (pinfunction "D6_14") (pintype "input"))
      (node (ref "E7") (pin "13") (pinfunction "D4_13") (pintype "input"))
    )
    (net (code "30") (name "ENT1") (class "Default")
      (node (ref "E10") (pin "8") (pinfunction "A4_8") (pintype "input"))
      (node (ref "E2") (pin "13") (pinfunction "QA_13") (pintype "output"))
      (node (ref "E36") (pin "4") (pinfunction "D2_4") (pintype "input"))
      (node (ref "E6") (pin "13") (pinfunction "D4_13") (pintype "input"))
    )
    (net (code "31") (name "ENT2") (class "Default")
      (node (ref "E1") (pin "13") (pinfunction "QA_13") (pintype "output"))
      (node (ref "E36") (pin "3") (pinfunction "D1_3") (pintype "input"))
      (node (ref "E5") (pin "13") (pinfunction "D4_13") (pintype "input"))
      (node (ref "E9") (pin "8") (pinfunction "A4_8") (pintype "input"))
    )
    (net (code "32") (name "GND") (class "Default")
      (node (ref "C1") (pin "2") (pinfunction "2_2") (pintype "passive"))
      (node (ref "C10") (pin "2") (pinfunction "2_2") (pintype "passive"))
      (node (ref "C11") (pin "2") (pinfunction "2_2") (pintype "passive"))
      (node (ref "C12") (pin "2") (pinfunction "2_2") (pintype "passive"))
      (node (ref "C13") (pin "2") (pinfunction "2_2") (pintype "passive"))
      (node (ref "C14") (pin "2") (pinfunction "2_2") (pintype "passive"))
      (node (ref "C15") (pin "2") (pinfunction "2_2") (pintype "passive"))
      (node (ref "C16") (pin "2") (pinfunction "2_2") (pintype "passive"))
      (node (ref "C17") (pin "2") (pinfunction "2_2") (pintype "passive"))
      (node (ref "C18") (pin "2") (pinfunction "2_2") (pintype "passive"))
      (node (ref "C19") (pin "2") (pinfunction "2_2") (pintype "passive"))
      (node (ref "C2") (pin "2") (pinfunction "2_2") (pintype "passive"))
      (node (ref "C20") (pin "2") (pinfunction "2_2") (pintype "passive"))
      (node (ref "C21") (pin "2") (pinfunction "2_2") (pintype "passive"))
      (node (ref "C22") (pin "2") (pinfunction "2_2") (pintype "passive"))
      (node (ref "C23") (pin "2") (pinfunction "2_2") (pintype "passive"))
      (node (ref "C24") (pin "2") (pinfunction "2_2") (pintype "passive"))
      (node (ref "C25") (pin "2") (pinfunction "2_2") (pintype "passive"))
      (node (ref "C26") (pin "2") (pinfunction "2_2") (pintype "passive"))
      (node (ref "C27") (pin "2") (pinfunction "2_2") (pintype "passive"))
      (node (ref "C28") (pin "2") (pinfunction "2_2") (pintype "passive"))
      (node (ref "C29") (pin "2") (pinfunction "2_2") (pintype "passive"))
      (node (ref "C3") (pin "2") (pinfunction "2_2") (pintype "passive"))
      (node (ref "C30") (pin "2") (pinfunction "2_2") (pintype "passive"))
      (node (ref "C31") (pin "2") (pinfunction "2_2") (pintype "passive"))
      (node (ref "C32") (pin "2") (pinfunction "2_2") (pintype "passive"))
      (node (ref "C33") (pin "2") (pinfunction "2_2") (pintype "passive"))
      (node (ref "C34") (pin "2") (pinfunction "2_2") (pintype "passive"))
      (node (ref "C35") (pin "2") (pinfunction "2_2") (pintype "passive"))
      (node (ref "C36") (pin "2") (pinfunction "2_2") (pintype "passive"))
      (node (ref "C38") (pin "-") (pinfunction "-_-") (pintype "passive"))
      (node (ref "C39") (pin "-") (pinfunction "-_-") (pintype "passive"))
      (node (ref "C4") (pin "2") (pinfunction "2_2") (pintype "passive"))
      (node (ref "C5") (pin "2") (pinfunction "2_2") (pintype "passive"))
      (node (ref "C6") (pin "2") (pinfunction "2_2") (pintype "passive"))
      (node (ref "C7") (pin "2") (pinfunction "2_2") (pintype "passive"))
      (node (ref "C8") (pin "2") (pinfunction "2_2") (pintype "passive"))
      (node (ref "C9") (pin "2") (pinfunction "2_2") (pintype "passive"))
      (node (ref "E1") (pin "3") (pinfunction "B_3") (pintype "input"))
      (node (ref "E1") (pin "4") (pinfunction "C_4") (pintype "input"))
      (node (ref "E1") (pin "5") (pinfunction "D_5") (pintype "input"))
      (node (ref "E17") (pin "1") (pinfunction "1G_1") (pintype "input"))
      (node (ref "E17") (pin "15") (pinfunction "2G_15") (pintype "input"))
      (node (ref "E18") (pin "1") (pinfunction "1G_1") (pintype "input"))
      (node (ref "E18") (pin "15") (pinfunction "2G_15") (pintype "input"))
      (node (ref "E19") (pin "1") (pinfunction "1G_1") (pintype "input"))
      (node (ref "E19") (pin "15") (pinfunction "2G_15") (pintype "input"))
      (node (ref "E2") (pin "3") (pinfunction "B_3") (pintype "input"))
      (node (ref "E2") (pin "4") (pinfunction "C_4") (pintype "input"))
      (node (ref "E2") (pin "5") (pinfunction "D_5") (pintype "input"))
      (node (ref "E25") (pin "3") (pinfunction "I0_3") (pintype "input"))
      (node (ref "E25") (pin "4") (pinfunction "I1_4") (pintype "input"))
      (node (ref "E3") (pin "3") (pinfunction "B_3") (pintype "input"))
      (node (ref "E3") (pin "4") (pinfunction "C_4") (pintype "input"))
      (node (ref "E3") (pin "5") (pinfunction "D_5") (pintype "input"))
      (node (ref "GND") (pin "1") (pinfunction "P_1") (pintype "passive"))
      (node (ref "J1") (pin "11") (pinfunction "11_11") (pintype "passive"))
      (node (ref "J1") (pin "13") (pinfunction "13_13") (pintype "passive"))
      (node (ref "J1") (pin "15") (pinfunction "15_15") (pintype "passive"))
      (node (ref "J1") (pin "17") (pinfunction "17_17") (pintype "passive"))
      (node (ref "J1") (pin "19") (pinfunction "19_19") (pintype "passive"))
      (node (ref "J1") (pin "21") (pinfunction "21_21") (pintype "passive"))
      (node (ref "J1") (pin "23") (pinfunction "23_23") (pintype "passive"))
      (node (ref "J1") (pin "25") (pinfunction "25_25") (pintype "passive"))
      (node (ref "J1") (pin "27") (pinfunction "27_27") (pintype "passive"))
      (node (ref "J1") (pin "29") (pinfunction "29_29") (pintype "passive"))
      (node (ref "J1") (pin "31") (pinfunction "31_31") (pintype "passive"))
      (node (ref "J1") (pin "33") (pinfunction "33_33") (pintype "passive"))
      (node (ref "J1") (pin "35") (pinfunction "35_35") (pintype "passive"))
      (node (ref "J1") (pin "37") (pinfunction "37_37") (pintype "passive"))
      (node (ref "J1") (pin "39") (pinfunction "39_39") (pintype "passive"))
      (node (ref "J2") (pin "11") (pinfunction "11_11") (pintype "passive"))
      (node (ref "J2") (pin "13") (pinfunction "13_13") (pintype "passive"))
      (node (ref "J2") (pin "15") (pinfunction "15_15") (pintype "passive"))
      (node (ref "J2") (pin "16") (pinfunction "16_16") (pintype "passive"))
      (node (ref "J2") (pin "17") (pinfunction "17_17") (pintype "passive"))
      (node (ref "J2") (pin "19") (pinfunction "19_19") (pintype "passive"))
      (node (ref "J2") (pin "21") (pinfunction "21_21") (pintype "passive"))
      (node (ref "J2") (pin "23") (pinfunction "23_23") (pintype "passive"))
      (node (ref "J2") (pin "25") (pinfunction "25_25") (pintype "passive"))
      (node (ref "J2") (pin "27") (pinfunction "27_27") (pintype "passive"))
      (node (ref "J2") (pin "29") (pinfunction "29_29") (pintype "passive"))
      (node (ref "J2") (pin "31") (pinfunction "31_31") (pintype "passive"))
      (node (ref "J2") (pin "33") (pinfunction "33_33") (pintype "passive"))
      (node (ref "J2") (pin "35") (pinfunction "35_35") (pintype "passive"))
      (node (ref "J2") (pin "37") (pinfunction "37_37") (pintype "passive"))
      (node (ref "J2") (pin "39") (pinfunction "39_39") (pintype "passive"))
      (node (ref "J3") (pin "8") (pinfunction "8_8") (pintype "passive"))
      (node (ref "J4") (pin "8") (pinfunction "8_8") (pintype "passive"))
      (node (ref "R1") (pin "1") (pinfunction "1_1") (pintype "passive"))
      (node (ref "R17") (pin "1") (pinfunction "1_1") (pintype "passive"))
      (node (ref "R18") (pin "1") (pinfunction "1_1") (pintype "passive"))
      (node (ref "R19") (pin "1") (pinfunction "1_1") (pintype "passive"))
      (node (ref "R2") (pin "1") (pinfunction "1_1") (pintype "passive"))
      (node (ref "R20") (pin "1") (pinfunction "1_1") (pintype "passive"))
      (node (ref "R21") (pin "1") (pinfunction "1_1") (pintype "passive"))
      (node (ref "R22") (pin "1") (pinfunction "1_1") (pintype "passive"))
      (node (ref "R23") (pin "1") (pinfunction "1_1") (pintype "passive"))
      (node (ref "R24") (pin "1") (pinfunction "1_1") (pintype "passive"))
      (node (ref "R27") (pin "1") (pinfunction "1_1") (pintype "passive"))
      (node (ref "R3") (pin "1") (pinfunction "1_1") (pintype "passive"))
      (node (ref "R30") (pin "1") (pinfunction "1_1") (pintype "passive"))
      (node (ref "R4") (pin "1") (pinfunction "1_1") (pintype "passive"))
    )
    (net (code "33") (name "KEYSTB") (class "Default")
      (node (ref "E24") (pin "1") (pinfunction "I_1") (pintype "input"))
      (node (ref "E8") (pin "5") (pinfunction "I1_5") (pintype "input"))
      (node (ref "J4") (pin "2") (pinfunction "2_2") (pintype "passive"))
    )
    (net (code "34") (name "LDSR") (class "Default")
      (node (ref "E33") (pin "13") (pinfunction "O_13") (pintype "output"))
      (node (ref "E5") (pin "9") (pinfunction "CLK_9") (pintype "input"))
      (node (ref "E6") (pin "9") (pinfunction "CLK_9") (pintype "input"))
      (node (ref "E7") (pin "9") (pinfunction "CLK_9") (pintype "input"))
    )
    (net (code "35") (name "MH0") (class "Default")
      (node (ref "E20") (pin "9") (pinfunction "Q_9") (pintype "output"))
      (node (ref "E22") (pin "11") (pinfunction "I0_11") (pintype "input"))
      (node (ref "E8") (pin "13") (pinfunction "I1_13") (pintype "input"))
    )
    (net (code "36") (name "MPXA") (class "Default")
      (node (ref "E17") (pin "14") (pinfunction "A_14") (pintype "input"))
      (node (ref "E18") (pin "14") (pinfunction "A_14") (pintype "input"))
      (node (ref "E19") (pin "14") (pinfunction "A_14") (pintype "input"))
      (node (ref "J4") (pin "14") (pinfunction "14_14") (pintype "passive"))
    )
    (net (code "37") (name "MPXB") (class "Default")
      (node (ref "E17") (pin "2") (pinfunction "B_2") (pintype "input"))
      (node (ref "E18") (pin "2") (pinfunction "B_2") (pintype "input"))
      (node (ref "E19") (pin "2") (pinfunction "B_2") (pintype "input"))
      (node (ref "J4") (pin "13") (pinfunction "13_13") (pintype "passive"))
    )
    (net (code "38") (name "NUM") (class "Default")
      (node (ref "E16") (pin "12") (pinfunction "D_12") (pintype "input"))
      (node (ref "E21") (pin "13") (pinfunction "I2_13") (pintype "input"))
      (node (ref "E8") (pin "4") (pinfunction "I0_4") (pintype "input"))
      (node (ref "J4") (pin "11") (pinfunction "11_11") (pintype "passive"))
    )
    (net (code "39") (name "NUMCLK") (class "Default")
      (node (ref "E1") (pin "8") (pinfunction "CK2_8") (pintype "input"))
      (node (ref "E1") (pin "9") (pinfunction "CK1_9") (pintype "input"))
      (node (ref "E2") (pin "8") (pinfunction "CK2_8") (pintype "input"))
      (node (ref "E2") (pin "9") (pinfunction "CK1_9") (pintype "input"))
      (node (ref "E3") (pin "8") (pinfunction "CK2_8") (pintype "input"))
      (node (ref "E3") (pin "9") (pinfunction "CK1_9") (pintype "input"))
      (node (ref "E8") (pin "6") (pinfunction "O_6") (pintype "output"))
    )
    (net (code "40") (name "Net-(E1A-QB)") (class "Default")
      (node (ref "E1") (pin "12") (pinfunction "QB_12") (pintype "output"))
      (node (ref "E5") (pin "12") (pinfunction "D3_12") (pintype "input"))
      (node (ref "E9") (pin "6") (pinfunction "A3_6") (pintype "input"))
    )
    (net (code "41") (name "Net-(E1A-QC)") (class "Default")
      (node (ref "E1") (pin "11") (pinfunction "QC_11") (pintype "output"))
      (node (ref "E5") (pin "5") (pinfunction "D2_5") (pintype "input"))
      (node (ref "E9") (pin "4") (pinfunction "A2_4") (pintype "input"))
    )
    (net (code "42") (name "Net-(E1A-QD)") (class "Default")
      (node (ref "E1") (pin "10") (pinfunction "QD_10") (pintype "output"))
      (node (ref "E5") (pin "4") (pinfunction "D1_4") (pintype "input"))
      (node (ref "E9") (pin "2") (pinfunction "A1_2") (pintype "input"))
    )
    (net (code "43") (name "Net-(E4B-C)") (class "Default")
      (node (ref "C37") (pin "2") (pinfunction "2_2") (pintype "passive"))
      (node (ref "C40") (pin "2") (pinfunction "2_2") (pintype "passive"))
      (node (ref "E4") (pin "6") (pinfunction "C_6") (pintype "input"))
    )
    (net (code "44") (name "Net-(E4B-Q)") (class "Default")
      (node (ref "E4") (pin "5") (pinfunction "Q_5") (pintype "output"))
      (node (ref "E8") (pin "10") (pinfunction "I1_10") (pintype "input"))
      (node (ref "E8") (pin "12") (pinfunction "I0_12") (pintype "input"))
    )
    (net (code "45") (name "Net-(E4B-R{slash}C)") (class "Default")
      (node (ref "C37") (pin "1") (pinfunction "1_1") (pintype "passive"))
      (node (ref "C40") (pin "1") (pinfunction "1_1") (pintype "passive"))
      (node (ref "E4") (pin "7") (pinfunction "R/C_7") (pintype "input"))
      (node (ref "R25") (pin "2") (pinfunction "2_2") (pintype "passive"))
    )
    (net (code "46") (name "Net-(E5A-Q1)") (class "Default")
      (node (ref "E5") (pin "2") (pinfunction "Q1_2") (pintype "output"))
      (node (ref "E9") (pin "17") (pinfunction "A4_17") (pintype "input"))
    )
    (net (code "47") (name "Net-(E5A-Q2)") (class "Default")
      (node (ref "E5") (pin "7") (pinfunction "Q2_7") (pintype "output"))
      (node (ref "E9") (pin "15") (pinfunction "A3_15") (pintype "input"))
    )
    (net (code "48") (name "Net-(E5A-Q3)") (class "Default")
      (node (ref "E5") (pin "10") (pinfunction "Q3_10") (pintype "output"))
      (node (ref "E9") (pin "13") (pinfunction "A2_13") (pintype "input"))
    )
    (net (code "49") (name "Net-(E5A-Q4)") (class "Default")
      (node (ref "E5") (pin "15") (pinfunction "Q4_15") (pintype "output"))
      (node (ref "E9") (pin "11") (pinfunction "A1_11") (pintype "input"))
    )
    (net (code "50") (name "Net-(E10A-A1)") (class "Default")
      (node (ref "E10") (pin "2") (pinfunction "A1_2") (pintype "input"))
      (node (ref "E2") (pin "10") (pinfunction "QD_10") (pintype "output"))
      (node (ref "E6") (pin "4") (pinfunction "D1_4") (pintype "input"))
    )
    (net (code "51") (name "Net-(E10A-A2)") (class "Default")
      (node (ref "E10") (pin "4") (pinfunction "A2_4") (pintype "input"))
      (node (ref "E2") (pin "11") (pinfunction "QC_11") (pintype "output"))
      (node (ref "E6") (pin "5") (pinfunction "D2_5") (pintype "input"))
    )
    (net (code "52") (name "Net-(E10A-A3)") (class "Default")
      (node (ref "E10") (pin "6") (pinfunction "A3_6") (pintype "input"))
      (node (ref "E2") (pin "12") (pinfunction "QB_12") (pintype "output"))
      (node (ref "E6") (pin "12") (pinfunction "D3_12") (pintype "input"))
    )
    (net (code "53") (name "Net-(E10B-A1)") (class "Default")
      (node (ref "E10") (pin "11") (pinfunction "A1_11") (pintype "input"))
      (node (ref "E6") (pin "15") (pinfunction "Q4_15") (pintype "output"))
    )
    (net (code "54") (name "Net-(E10B-A2)") (class "Default")
      (node (ref "E10") (pin "13") (pinfunction "A2_13") (pintype "input"))
      (node (ref "E6") (pin "10") (pinfunction "Q3_10") (pintype "output"))
    )
    (net (code "55") (name "Net-(E10B-A3)") (class "Default")
      (node (ref "E10") (pin "15") (pinfunction "A3_15") (pintype "input"))
      (node (ref "E6") (pin "7") (pinfunction "Q2_7") (pintype "output"))
    )
    (net (code "56") (name "Net-(E10B-A4)") (class "Default")
      (node (ref "E10") (pin "17") (pinfunction "A4_17") (pintype "input"))
      (node (ref "E6") (pin "2") (pinfunction "Q1_2") (pintype "output"))
    )
    (net (code "57") (name "Net-(E11A-A1)") (class "Default")
      (node (ref "E11") (pin "2") (pinfunction "A1_2") (pintype "input"))
      (node (ref "E3") (pin "10") (pinfunction "QD_10") (pintype "output"))
      (node (ref "E7") (pin "4") (pinfunction "D1_4") (pintype "input"))
    )
    (net (code "58") (name "Net-(E11A-A2)") (class "Default")
      (node (ref "E11") (pin "4") (pinfunction "A2_4") (pintype "input"))
      (node (ref "E3") (pin "11") (pinfunction "QC_11") (pintype "output"))
      (node (ref "E7") (pin "5") (pinfunction "D2_5") (pintype "input"))
    )
    (net (code "59") (name "Net-(E11A-A3)") (class "Default")
      (node (ref "E11") (pin "6") (pinfunction "A3_6") (pintype "input"))
      (node (ref "E3") (pin "12") (pinfunction "QB_12") (pintype "output"))
      (node (ref "E7") (pin "12") (pinfunction "D3_12") (pintype "input"))
    )
    (net (code "60") (name "Net-(E11B-A1)") (class "Default")
      (node (ref "E11") (pin "11") (pinfunction "A1_11") (pintype "input"))
      (node (ref "E7") (pin "15") (pinfunction "Q4_15") (pintype "output"))
    )
    (net (code "61") (name "Net-(E11B-A2)") (class "Default")
      (node (ref "E11") (pin "13") (pinfunction "A2_13") (pintype "input"))
      (node (ref "E7") (pin "10") (pinfunction "Q3_10") (pintype "output"))
    )
    (net (code "62") (name "Net-(E11B-A3)") (class "Default")
      (node (ref "E11") (pin "15") (pinfunction "A3_15") (pintype "input"))
      (node (ref "E7") (pin "7") (pinfunction "Q2_7") (pintype "output"))
    )
    (net (code "63") (name "Net-(E11B-A4)") (class "Default")
      (node (ref "E11") (pin "17") (pinfunction "A4_17") (pintype "input"))
      (node (ref "E7") (pin "2") (pinfunction "Q1_2") (pintype "output"))
    )
    (net (code "64") (name "Net-(E12A-Q1)") (class "Default")
      (node (ref "E12") (pin "2") (pinfunction "Q1_2") (pintype "output"))
      (node (ref "E17") (pin "4") (pinfunction "1C2_4") (pintype "input"))
    )
    (net (code "65") (name "Net-(E12A-Q2)") (class "Default")
      (node (ref "E12") (pin "5") (pinfunction "Q2_5") (pintype "output"))
      (node (ref "E17") (pin "6") (pinfunction "1C0_6") (pintype "input"))
    )
    (net (code "66") (name "Net-(E12A-Q3)") (class "Default")
      (node (ref "E12") (pin "7") (pinfunction "Q3_7") (pintype "output"))
      (node (ref "E17") (pin "13") (pinfunction "2C3_13") (pintype "input"))
    )
    (net (code "67") (name "Net-(E12A-Q4)") (class "Default")
      (node (ref "E12") (pin "10") (pinfunction "Q4_10") (pintype "output"))
      (node (ref "E17") (pin "11") (pinfunction "2C1_11") (pintype "input"))
    )
    (net (code "68") (name "Net-(E12A-Q5)") (class "Default")
      (node (ref "E12") (pin "12") (pinfunction "Q5_12") (pintype "output"))
      (node (ref "E17") (pin "12") (pinfunction "2C2_12") (pintype "input"))
    )
    (net (code "69") (name "Net-(E12A-Q6)") (class "Default")
      (node (ref "E12") (pin "15") (pinfunction "Q6_15") (pintype "output"))
      (node (ref "E17") (pin "10") (pinfunction "2C0_10") (pintype "input"))
    )
    (net (code "70") (name "Net-(E13A-Q1)") (class "Default")
      (node (ref "E13") (pin "2") (pinfunction "Q1_2") (pintype "output"))
      (node (ref "E19") (pin "12") (pinfunction "2C2_12") (pintype "input"))
    )
    (net (code "71") (name "Net-(E13A-Q2)") (class "Default")
      (node (ref "E13") (pin "5") (pinfunction "Q2_5") (pintype "output"))
      (node (ref "E19") (pin "10") (pinfunction "2C0_10") (pintype "input"))
    )
    (net (code "72") (name "Net-(E13A-Q3)") (class "Default")
      (node (ref "E13") (pin "7") (pinfunction "Q3_7") (pintype "output"))
      (node (ref "E18") (pin "3") (pinfunction "1C3_3") (pintype "input"))
    )
    (net (code "73") (name "Net-(E13A-Q4)") (class "Default")
      (node (ref "E13") (pin "10") (pinfunction "Q4_10") (pintype "output"))
      (node (ref "E18") (pin "5") (pinfunction "1C1_5") (pintype "input"))
    )
    (net (code "74") (name "Net-(E13A-Q5)") (class "Default")
      (node (ref "E13") (pin "12") (pinfunction "Q5_12") (pintype "output"))
      (node (ref "E18") (pin "4") (pinfunction "1C2_4") (pintype "input"))
    )
    (net (code "75") (name "Net-(E13A-Q6)") (class "Default")
      (node (ref "E13") (pin "15") (pinfunction "Q6_15") (pintype "output"))
      (node (ref "E18") (pin "6") (pinfunction "1C0_6") (pintype "input"))
    )
    (net (code "76") (name "Net-(E14A-Q1)") (class "Default")
      (node (ref "E14") (pin "2") (pinfunction "Q1_2") (pintype "output"))
      (node (ref "E18") (pin "13") (pinfunction "2C3_13") (pintype "input"))
    )
    (net (code "77") (name "Net-(E14A-Q2)") (class "Default")
      (node (ref "E14") (pin "5") (pinfunction "Q2_5") (pintype "output"))
      (node (ref "E18") (pin "11") (pinfunction "2C1_11") (pintype "input"))
    )
    (net (code "78") (name "Net-(E14A-Q3)") (class "Default")
      (node (ref "E14") (pin "7") (pinfunction "Q3_7") (pintype "output"))
      (node (ref "E18") (pin "12") (pinfunction "2C2_12") (pintype "input"))
    )
    (net (code "79") (name "Net-(E14A-Q4)") (class "Default")
      (node (ref "E14") (pin "10") (pinfunction "Q4_10") (pintype "output"))
      (node (ref "E18") (pin "10") (pinfunction "2C0_10") (pintype "input"))
    )
    (net (code "80") (name "Net-(E14A-Q5)") (class "Default")
      (node (ref "E14") (pin "12") (pinfunction "Q5_12") (pintype "output"))
      (node (ref "E17") (pin "3") (pinfunction "1C3_3") (pintype "input"))
    )
    (net (code "81") (name "Net-(E14A-Q6)") (class "Default")
      (node (ref "E14") (pin "15") (pinfunction "Q6_15") (pintype "output"))
      (node (ref "E17") (pin "5") (pinfunction "1C1_5") (pintype "input"))
    )
    (net (code "82") (name "Net-(E15A-Q1)") (class "Default")
      (node (ref "E15") (pin "2") (pinfunction "Q1_2") (pintype "output"))
      (node (ref "E19") (pin "3") (pinfunction "1C3_3") (pintype "input"))
    )
    (net (code "83") (name "Net-(E15A-Q2)") (class "Default")
      (node (ref "E15") (pin "5") (pinfunction "Q2_5") (pintype "output"))
      (node (ref "E19") (pin "5") (pinfunction "1C1_5") (pintype "input"))
    )
    (net (code "84") (name "Net-(E15A-Q3)") (class "Default")
      (node (ref "E15") (pin "7") (pinfunction "Q3_7") (pintype "output"))
      (node (ref "E19") (pin "4") (pinfunction "1C2_4") (pintype "input"))
    )
    (net (code "85") (name "Net-(E15A-Q4)") (class "Default")
      (node (ref "E15") (pin "10") (pinfunction "Q4_10") (pintype "output"))
      (node (ref "E19") (pin "6") (pinfunction "1C0_6") (pintype "input"))
    )
    (net (code "86") (name "Net-(E15A-Q5)") (class "Default")
      (node (ref "E15") (pin "12") (pinfunction "Q5_12") (pintype "output"))
      (node (ref "E19") (pin "13") (pinfunction "2C3_13") (pintype "input"))
    )
    (net (code "87") (name "Net-(E15A-Q6)") (class "Default")
      (node (ref "E15") (pin "15") (pinfunction "Q6_15") (pintype "output"))
      (node (ref "E19") (pin "11") (pinfunction "2C1_11") (pintype "input"))
    )
    (net (code "88") (name "Net-(E16A-CLK)") (class "Default")
      (node (ref "E16") (pin "3") (pinfunction "CLK_3") (pintype "input"))
      (node (ref "E21") (pin "12") (pinfunction "O_12") (pintype "output"))
    )
    (net (code "89") (name "Net-(E20A-PRE)") (class "Default")
      (node (ref "E20") (pin "4") (pinfunction "PRE_4") (pintype "input"))
      (node (ref "E26") (pin "8") (pinfunction "~{Q4}_8") (pintype "output"))
    )
    (net (code "90") (name "Net-(E20B-CLK)") (class "Default")
      (node (ref "E20") (pin "11") (pinfunction "CLK_11") (pintype "input"))
      (node (ref "E22") (pin "1") (pinfunction "O_1") (pintype "output"))
      (node (ref "E4") (pin "9") (pinfunction "A_9") (pintype "input"))
    )
    (net (code "91") (name "Net-(E21A-I0)") (class "Default")
      (node (ref "E21") (pin "1") (pinfunction "I0_1") (pintype "input"))
      (node (ref "E24") (pin "4") (pinfunction "O_4") (pintype "output"))
    )
    (net (code "92") (name "Net-(E21B-I0)") (class "Default")
      (node (ref "E21") (pin "3") (pinfunction "I0_3") (pintype "input"))
      (node (ref "E21") (pin "4") (pinfunction "I1_4") (pintype "input"))
      (node (ref "E22") (pin "4") (pinfunction "O_4") (pintype "output"))
    )
    (net (code "93") (name "Net-(E21C-O)") (class "Default")
      (node (ref "E21") (pin "8") (pinfunction "O_8") (pintype "output"))
      (node (ref "E23") (pin "9") (pinfunction "I_9") (pintype "input"))
    )
    (net (code "94") (name "Net-(E22A-I0)") (class "Default")
      (node (ref "E22") (pin "2") (pinfunction "I0_2") (pintype "input"))
      (node (ref "E32") (pin "6") (pinfunction "O_6") (pintype "output"))
    )
    (net (code "95") (name "Net-(E22A-I1)") (class "Default")
      (node (ref "E22") (pin "3") (pinfunction "I1_3") (pintype "input"))
      (node (ref "E33") (pin "1") (pinfunction "O_1") (pintype "output"))
    )
    (net (code "96") (name "Net-(E22B-I0)") (class "Default")
      (node (ref "E22") (pin "5") (pinfunction "I0_5") (pintype "input"))
      (node (ref "E8") (pin "3") (pinfunction "O_3") (pintype "output"))
    )
    (net (code "97") (name "Net-(E22C-I0)") (class "Default")
      (node (ref "E22") (pin "8") (pinfunction "I0_8") (pintype "input"))
      (node (ref "E25") (pin "12") (pinfunction "O_12") (pintype "output"))
    )
    (net (code "98") (name "Net-(E22C-I1)") (class "Default")
      (node (ref "E22") (pin "9") (pinfunction "I1_9") (pintype "input"))
      (node (ref "E25") (pin "8") (pinfunction "O_8") (pintype "output"))
    )
    (net (code "99") (name "Net-(E22C-O)") (class "Default")
      (node (ref "E22") (pin "10") (pinfunction "O_10") (pintype "output"))
      (node (ref "E29") (pin "4") (pinfunction "G2A_4") (pintype "input"))
      (node (ref "E29") (pin "5") (pinfunction "G2B_5") (pintype "input"))
      (node (ref "E31") (pin "15") (pinfunction "2G_15") (pintype "input"))
    )
    (net (code "100") (name "Net-(E22D-O)") (class "Default")
      (node (ref "E22") (pin "13") (pinfunction "O_13") (pintype "output"))
      (node (ref "E30") (pin "4") (pinfunction "I0_4") (pintype "input"))
    )
    (net (code "101") (name "Net-(E23A-I)") (class "Default")
      (node (ref "E23") (pin "1") (pinfunction "I_1") (pintype "input"))
      (node (ref "E33") (pin "4") (pinfunction "O_4") (pintype "output"))
    )
    (net (code "102") (name "Net-(E23E-I)") (class "Default")
      (node (ref "E23") (pin "11") (pinfunction "I_11") (pintype "input"))
      (node (ref "E24") (pin "10") (pinfunction "O_10") (pintype "output"))
    )
    (net (code "103") (name "Net-(E23F-I)") (class "Default")
      (node (ref "E23") (pin "13") (pinfunction "I_13") (pintype "input"))
      (node (ref "E25") (pin "6") (pinfunction "O_6") (pintype "output"))
    )
    (net (code "104") (name "Net-(E24D-O)") (class "Default")
      (node (ref "E24") (pin "8") (pinfunction "O_8") (pintype "output"))
      (node (ref "E32") (pin "5") (pinfunction "I1_5") (pintype "input"))
    )
    (net (code "105") (name "Net-(E24F-O)") (class "Default")
      (node (ref "E24") (pin "12") (pinfunction "O_12") (pintype "output"))
      (node (ref "E25") (pin "10") (pinfunction "I1_10") (pintype "input"))
      (node (ref "E28") (pin "1") (pinfunction "1G_1") (pintype "input"))
      (node (ref "E28") (pin "15") (pinfunction "2G_15") (pintype "input"))
      (node (ref "E33") (pin "6") (pinfunction "I1_6") (pintype "input"))
    )
    (net (code "106") (name "Net-(E25A-I0)") (class "Default")
      (node (ref "E25") (pin "1") (pinfunction "I0_1") (pintype "input"))
      (node (ref "E26") (pin "16") (pinfunction "Q1_16") (pintype "output"))
      (node (ref "E29") (pin "3") (pinfunction "C_3") (pintype "input"))
    )
    (net (code "107") (name "Net-(E25A-I2)") (class "Default")
      (node (ref "E25") (pin "13") (pinfunction "I2_13") (pintype "input"))
      (node (ref "E26") (pin "15") (pinfunction "Q2_15") (pintype "output"))
      (node (ref "E27") (pin "3") (pinfunction "I_3") (pintype "input"))
      (node (ref "E29") (pin "2") (pinfunction "B_2") (pintype "input"))
      (node (ref "E30") (pin "1") (pinfunction "I0_1") (pintype "input"))
    )
    (net (code "108") (name "Net-(E25B-I2)") (class "Default")
      (node (ref "D1") (pin "A") (pinfunction "A_A") (pintype "passive"))
      (node (ref "D2") (pin "A") (pinfunction "A_A") (pintype "passive"))
      (node (ref "E25") (pin "5") (pinfunction "I2_5") (pintype "input"))
      (node (ref "R37") (pin "1") (pinfunction "1_1") (pintype "passive"))
    )
    (net (code "109") (name "Net-(E25C-I0)") (class "Default")
      (node (ref "E25") (pin "9") (pinfunction "I0_9") (pintype "input"))
      (node (ref "E26") (pin "9") (pinfunction "Q4_9") (pintype "output"))
    )
    (net (code "110") (name "Net-(E26A-Q3)") (class "Default")
      (node (ref "E26") (pin "10") (pinfunction "Q3_10") (pintype "output"))
      (node (ref "E29") (pin "1") (pinfunction "A_1") (pintype "input"))
    )
    (net (code "111") (name "Net-(E27A-O)") (class "Default")
      (node (ref "E27") (pin "2") (pinfunction "O_2") (pintype "output"))
      (node (ref "E30") (pin "12") (pinfunction "I0_12") (pintype "input"))
    )
    (net (code "112") (name "Net-(E27B-O)") (class "Default")
      (node (ref "E27") (pin "4") (pinfunction "O_4") (pintype "output"))
      (node (ref "E31") (pin "12") (pinfunction "2A1_12") (pintype "input"))
    )
    (net (code "113") (name "Net-(E27C-O)") (class "Default")
      (node (ref "E27") (pin "6") (pinfunction "O_6") (pintype "output"))
      (node (ref "E30") (pin "13") (pinfunction "I1_13") (pintype "input"))
    )
    (net (code "114") (name "Net-(E28A-1A1)") (class "Default")
      (node (ref "E28") (pin "2") (pinfunction "1A1_2") (pintype "input"))
      (node (ref "E29") (pin "9") (pinfunction "Y6_9") (pintype "output"))
      (node (ref "E32") (pin "2") (pinfunction "I1_2") (pintype "input"))
    )
    (net (code "115") (name "Net-(E28A-1A2)") (class "Default")
      (node (ref "E28") (pin "4") (pinfunction "1A2_4") (pintype "input"))
      (node (ref "E29") (pin "7") (pinfunction "Y7_7") (pintype "output"))
      (node (ref "E30") (pin "10") (pinfunction "I1_10") (pintype "input"))
      (node (ref "E32") (pin "1") (pinfunction "I0_1") (pintype "input"))
    )
    (net (code "116") (name "Net-(E28A-1A3)") (class "Default")
      (node (ref "E28") (pin "6") (pinfunction "1A3_6") (pintype "input"))
      (node (ref "E30") (pin "9") (pinfunction "I0_9") (pintype "input"))
      (node (ref "E31") (pin "6") (pinfunction "1A3_6") (pintype "input"))
      (node (ref "E32") (pin "8") (pinfunction "O_8") (pintype "output"))
      (node (ref "E33") (pin "5") (pinfunction "I0_5") (pintype "input"))
    )
    (net (code "117") (name "Net-(E28A-2A2)") (class "Default")
      (node (ref "E28") (pin "14") (pinfunction "2A2_14") (pintype "input"))
      (node (ref "E30") (pin "11") (pinfunction "O_11") (pintype "output"))
    )
    (net (code "118") (name "Net-(E29A-Y0)") (class "Default")
      (node (ref "E29") (pin "15") (pinfunction "Y0_15") (pintype "output"))
      (node (ref "E33") (pin "8") (pinfunction "I0_8") (pintype "input"))
    )
    (net (code "119") (name "Net-(E29A-Y1)") (class "Default")
      (node (ref "E29") (pin "14") (pinfunction "Y1_14") (pintype "output"))
      (node (ref "E33") (pin "12") (pinfunction "I1_12") (pintype "input"))
    )
    (net (code "120") (name "Net-(E29A-Y2)") (class "Default")
      (node (ref "E29") (pin "13") (pinfunction "Y2_13") (pintype "output"))
      (node (ref "E30") (pin "2") (pinfunction "I1_2") (pintype "input"))
      (node (ref "E32") (pin "10") (pinfunction "I1_10") (pintype "input"))
    )
    (net (code "121") (name "Net-(E29A-Y3)") (class "Default")
      (node (ref "E29") (pin "12") (pinfunction "Y3_12") (pintype "output"))
      (node (ref "E32") (pin "9") (pinfunction "I0_9") (pintype "input"))
    )
    (net (code "122") (name "Net-(E29A-Y4)") (class "Default")
      (node (ref "E29") (pin "11") (pinfunction "Y4_11") (pintype "output"))
      (node (ref "E31") (pin "10") (pinfunction "1A4_10") (pintype "input"))
    )
    (net (code "123") (name "Net-(E29A-Y5)") (class "Default")
      (node (ref "E29") (pin "10") (pinfunction "Y5_10") (pintype "output"))
      (node (ref "E31") (pin "2") (pinfunction "1A1_2") (pintype "input"))
    )
    (net (code "124") (name "Net-(E30A-O)") (class "Default")
      (node (ref "E30") (pin "3") (pinfunction "O_3") (pintype "output"))
      (node (ref "E31") (pin "14") (pinfunction "2A2_14") (pintype "input"))
    )
    (net (code "125") (name "Net-(E30B-O)") (class "Default")
      (node (ref "E30") (pin "6") (pinfunction "O_6") (pintype "output"))
      (node (ref "E34") (pin "1") (pinfunction "1G_1") (pintype "input"))
      (node (ref "E34") (pin "15") (pinfunction "2G_15") (pintype "input"))
      (node (ref "E35") (pin "4") (pinfunction "G2A_4") (pintype "input"))
      (node (ref "E35") (pin "5") (pinfunction "G2B_5") (pintype "input"))
    )
    (net (code "126") (name "Net-(E31A-1A2)") (class "Default")
      (node (ref "E31") (pin "4") (pinfunction "1A2_4") (pintype "input"))
      (node (ref "E32") (pin "3") (pinfunction "O_3") (pintype "output"))
    )
    (net (code "127") (name "Net-(E31A-1Y1)") (class "Default")
      (node (ref "D2") (pin "C") (pinfunction "C_C") (pintype "passive"))
      (node (ref "E31") (pin "3") (pinfunction "1Y1_3") (pintype "tri_state"))
    )
    (net (code "128") (name "Net-(E31A-1Y2)") (class "Default")
      (node (ref "D1") (pin "C") (pinfunction "C_C") (pintype "passive"))
      (node (ref "E31") (pin "5") (pinfunction "1Y2_5") (pintype "tri_state"))
    )
    (net (code "129") (name "Net-(E32D-I0)") (class "Default")
      (node (ref "E32") (pin "12") (pinfunction "I0_12") (pintype "input"))
      (node (ref "E35") (pin "11") (pinfunction "Y4_11") (pintype "output"))
    )
    (net (code "130") (name "Net-(E33C-O)") (class "Default")
      (node (ref "E33") (pin "10") (pinfunction "O_10") (pintype "output"))
      (node (ref "E36") (pin "9") (pinfunction "CLK_9") (pintype "input"))
    )
    (net (code "131") (name "Net-(E34A-1A3)") (class "Default")
      (node (ref "E34") (pin "6") (pinfunction "1A3_6") (pintype "input"))
      (node (ref "E35") (pin "9") (pinfunction "Y6_9") (pintype "output"))
    )
    (net (code "132") (name "Net-(E34A-2A1)") (class "Default")
      (node (ref "E34") (pin "12") (pinfunction "2A1_12") (pintype "input"))
      (node (ref "E35") (pin "10") (pinfunction "Y5_10") (pintype "output"))
    )
    (net (code "133") (name "POWCK") (class "Default")
      (node (ref "E24") (pin "11") (pinfunction "I_11") (pintype "input"))
      (node (ref "J2") (pin "28") (pinfunction "28_28") (pintype "passive"))
      (node (ref "R33") (pin "1") (pinfunction "1_1") (pintype "passive"))
    )
    (net (code "134") (name "THIS") (class "Default")
      (node (ref "E20") (pin "5") (pinfunction "Q_5") (pintype "output"))
      (node (ref "E28") (pin "12") (pinfunction "2A1_12") (pintype "input"))
    )
    (net (code "135") (name "VCC") (class "Default")
      (node (ref "C1") (pin "1") (pinfunction "1_1") (pintype "passive"))
      (node (ref "C10") (pin "1") (pinfunction "1_1") (pintype "passive"))
      (node (ref "C11") (pin "1") (pinfunction "1_1") (pintype "passive"))
      (node (ref "C12") (pin "1") (pinfunction "1_1") (pintype "passive"))
      (node (ref "C13") (pin "1") (pinfunction "1_1") (pintype "passive"))
      (node (ref "C14") (pin "1") (pinfunction "1_1") (pintype "passive"))
      (node (ref "C15") (pin "1") (pinfunction "1_1") (pintype "passive"))
      (node (ref "C16") (pin "1") (pinfunction "1_1") (pintype "passive"))
      (node (ref "C17") (pin "1") (pinfunction "1_1") (pintype "passive"))
      (node (ref "C18") (pin "1") (pinfunction "1_1") (pintype "passive"))
      (node (ref "C19") (pin "1") (pinfunction "1_1") (pintype "passive"))
      (node (ref "C2") (pin "1") (pinfunction "1_1") (pintype "passive"))
      (node (ref "C20") (pin "1") (pinfunction "1_1") (pintype "passive"))
      (node (ref "C21") (pin "1") (pinfunction "1_1") (pintype "passive"))
      (node (ref "C22") (pin "1") (pinfunction "1_1") (pintype "passive"))
      (node (ref "C23") (pin "1") (pinfunction "1_1") (pintype "passive"))
      (node (ref "C24") (pin "1") (pinfunction "1_1") (pintype "passive"))
      (node (ref "C25") (pin "1") (pinfunction "1_1") (pintype "passive"))
      (node (ref "C26") (pin "1") (pinfunction "1_1") (pintype "passive"))
      (node (ref "C27") (pin "1") (pinfunction "1_1") (pintype "passive"))
      (node (ref "C28") (pin "1") (pinfunction "1_1") (pintype "passive"))
      (node (ref "C29") (pin "1") (pinfunction "1_1") (pintype "passive"))
      (node (ref "C3") (pin "1") (pinfunction "1_1") (pintype "passive"))
      (node (ref "C30") (pin "1") (pinfunction "1_1") (pintype "passive"))
      (node (ref "C31") (pin "1") (pinfunction "1_1") (pintype "passive"))
      (node (ref "C32") (pin "1") (pinfunction "1_1") (pintype "passive"))
      (node (ref "C33") (pin "1") (pinfunction "1_1") (pintype "passive"))
      (node (ref "C34") (pin "1") (pinfunction "1_1") (pintype "passive"))
      (node (ref "C35") (pin "1") (pinfunction "1_1") (pintype "passive"))
      (node (ref "C36") (pin "1") (pinfunction "1_1") (pintype "passive"))
      (node (ref "C38") (pin "+") (pinfunction "+_+") (pintype "passive"))
      (node (ref "C39") (pin "+") (pinfunction "+_+") (pintype "passive"))
      (node (ref "C4") (pin "1") (pinfunction "1_1") (pintype "passive"))
      (node (ref "C5") (pin "1") (pinfunction "1_1") (pintype "passive"))
      (node (ref "C6") (pin "1") (pinfunction "1_1") (pintype "passive"))
      (node (ref "C7") (pin "1") (pinfunction "1_1") (pintype "passive"))
      (node (ref "C8") (pin "1") (pinfunction "1_1") (pintype "passive"))
      (node (ref "C9") (pin "1") (pinfunction "1_1") (pintype "passive"))
      (node (ref "E16") (pin "10") (pinfunction "PRE_10") (pintype "input"))
      (node (ref "E16") (pin "4") (pinfunction "PRE_4") (pintype "input"))
      (node (ref "E20") (pin "10") (pinfunction "PRE_10") (pintype "input"))
      (node (ref "E29") (pin "6") (pinfunction "G1_6") (pintype "input"))
      (node (ref "E34") (pin "10") (pinfunction "1A4_10") (pintype "input"))
      (node (ref "E35") (pin "6") (pinfunction "G1_6") (pintype "input"))
      (node (ref "E36") (pin "1") (pinfunction "CLR_1") (pintype "input"))
      (node (ref "E36") (pin "11") (pinfunction "D4_11") (pintype "input"))
      (node (ref "E36") (pin "13") (pinfunction "D5_13") (pintype "input"))
      (node (ref "E36") (pin "6") (pinfunction "D3_6") (pintype "input"))
      (node (ref "E4") (pin "10") (pinfunction "B_10") (pintype "input"))
      (node (ref "E4") (pin "11") (pinfunction "CLR_11") (pintype "input"))
      (node (ref "J1") (pin "1") (pinfunction "1_1") (pintype "passive"))
      (node (ref "J1") (pin "2") (pinfunction "2_2") (pintype "passive"))
      (node (ref "J1") (pin "3") (pinfunction "3_3") (pintype "passive"))
      (node (ref "J1") (pin "4") (pinfunction "4_4") (pintype "passive"))
      (node (ref "J1") (pin "5") (pinfunction "5_5") (pintype "passive"))
      (node (ref "J1") (pin "7") (pinfunction "7_7") (pintype "passive"))
      (node (ref "J1") (pin "9") (pinfunction "9_9") (pintype "passive"))
      (node (ref "J2") (pin "1") (pinfunction "1_1") (pintype "passive"))
      (node (ref "J2") (pin "3") (pinfunction "3_3") (pintype "passive"))
      (node (ref "J2") (pin "5") (pinfunction "5_5") (pintype "passive"))
      (node (ref "J2") (pin "7") (pinfunction "7_7") (pintype "passive"))
      (node (ref "J2") (pin "9") (pinfunction "9_9") (pintype "passive"))
      (node (ref "J3") (pin "16") (pinfunction "16_16") (pintype "passive"))
      (node (ref "J4") (pin "16") (pinfunction "16_16") (pintype "passive"))
      (node (ref "R10") (pin "2") (pinfunction "2_2") (pintype "passive"))
      (node (ref "R11") (pin "2") (pinfunction "2_2") (pintype "passive"))
      (node (ref "R12") (pin "2") (pinfunction "2_2") (pintype "passive"))
      (node (ref "R13") (pin "2") (pinfunction "2_2") (pintype "passive"))
      (node (ref "R14") (pin "2") (pinfunction "2_2") (pintype "passive"))
      (node (ref "R15") (pin "2") (pinfunction "2_2") (pintype "passive"))
      (node (ref "R16") (pin "2") (pinfunction "2_2") (pintype "passive"))
      (node (ref "R25") (pin "1") (pinfunction "1_1") (pintype "passive"))
      (node (ref "R26") (pin "2") (pinfunction "2_2") (pintype "passive"))
      (node (ref "R28") (pin "2") (pinfunction "2_2") (pintype "passive"))
      (node (ref "R29") (pin "2") (pinfunction "2_2") (pintype "passive"))
      (node (ref "R31") (pin "2") (pinfunction "2_2") (pintype "passive"))
      (node (ref "R32") (pin "2") (pinfunction "2_2") (pintype "passive"))
      (node (ref "R33") (pin "2") (pinfunction "2_2") (pintype "passive"))
      (node (ref "R34") (pin "1") (pinfunction "1_1") (pintype "passive"))
      (node (ref "R35") (pin "1") (pinfunction "1_1") (pintype "passive"))
      (node (ref "R36") (pin "1") (pinfunction "1_1") (pintype "passive"))
      (node (ref "R37") (pin "2") (pinfunction "2_2") (pintype "passive"))
      (node (ref "R5") (pin "2") (pinfunction "2_2") (pintype "passive"))
      (node (ref "R6") (pin "2") (pinfunction "2_2") (pintype "passive"))
      (node (ref "R7") (pin "2") (pinfunction "2_2") (pintype "passive"))
      (node (ref "R8") (pin "2") (pinfunction "2_2") (pintype "passive"))
      (node (ref "R9") (pin "2") (pinfunction "2_2") (pintype "passive"))
      (node (ref "VCC") (pin "1") (pinfunction "P_1") (pintype "passive"))
    )
    (net (code "136") (name "unconnected-(E4B-~{Q}-Pad12)") (class "Default")
      (node (ref "E4") (pin "12") (pinfunction "~{Q}_12") (pintype "output"))
    )
    (net (code "137") (name "unconnected-(E5A-~{Q1}-Pad3)") (class "Default")
      (node (ref "E5") (pin "3") (pinfunction "~{Q1}_3") (pintype "output"))
    )
    (net (code "138") (name "unconnected-(E5A-~{Q2}-Pad6)") (class "Default")
      (node (ref "E5") (pin "6") (pinfunction "~{Q2}_6") (pintype "output"))
    )
    (net (code "139") (name "unconnected-(E5A-~{Q3}-Pad11)") (class "Default")
      (node (ref "E5") (pin "11") (pinfunction "~{Q3}_11") (pintype "output"))
    )
    (net (code "140") (name "unconnected-(E5A-~{Q4}-Pad14)") (class "Default")
      (node (ref "E5") (pin "14") (pinfunction "~{Q4}_14") (pintype "output"))
    )
    (net (code "141") (name "unconnected-(E6A-~{Q1}-Pad3)") (class "Default")
      (node (ref "E6") (pin "3") (pinfunction "~{Q1}_3") (pintype "output"))
    )
    (net (code "142") (name "unconnected-(E6A-~{Q2}-Pad6)") (class "Default")
      (node (ref "E6") (pin "6") (pinfunction "~{Q2}_6") (pintype "output"))
    )
    (net (code "143") (name "unconnected-(E6A-~{Q3}-Pad11)") (class "Default")
      (node (ref "E6") (pin "11") (pinfunction "~{Q3}_11") (pintype "output"))
    )
    (net (code "144") (name "unconnected-(E6A-~{Q4}-Pad14)") (class "Default")
      (node (ref "E6") (pin "14") (pinfunction "~{Q4}_14") (pintype "output"))
    )
    (net (code "145") (name "unconnected-(E7A-~{Q1}-Pad3)") (class "Default")
      (node (ref "E7") (pin "3") (pinfunction "~{Q1}_3") (pintype "output"))
    )
    (net (code "146") (name "unconnected-(E7A-~{Q2}-Pad6)") (class "Default")
      (node (ref "E7") (pin "6") (pinfunction "~{Q2}_6") (pintype "output"))
    )
    (net (code "147") (name "unconnected-(E7A-~{Q3}-Pad11)") (class "Default")
      (node (ref "E7") (pin "11") (pinfunction "~{Q3}_11") (pintype "output"))
    )
    (net (code "148") (name "unconnected-(E7A-~{Q4}-Pad14)") (class "Default")
      (node (ref "E7") (pin "14") (pinfunction "~{Q4}_14") (pintype "output"))
    )
    (net (code "149") (name "unconnected-(E16A-Q-Pad5)") (class "Default")
      (node (ref "E16") (pin "5") (pinfunction "Q_5") (pintype "output"))
    )
    (net (code "150") (name "unconnected-(E20A-~{Q}-Pad6)") (class "Default")
      (node (ref "E20") (pin "6") (pinfunction "~{Q}_6") (pintype "output"))
    )
    (net (code "151") (name "unconnected-(E26A-~{Q1}-Pad1)") (class "Default")
      (node (ref "E26") (pin "1") (pinfunction "~{Q1}_1") (pintype "output"))
    )
    (net (code "152") (name "unconnected-(E26A-~{Q2}-Pad14)") (class "Default")
      (node (ref "E26") (pin "14") (pinfunction "~{Q2}_14") (pintype "output"))
    )
    (net (code "153") (name "unconnected-(E26A-~{Q3}-Pad11)") (class "Default")
      (node (ref "E26") (pin "11") (pinfunction "~{Q3}_11") (pintype "output"))
    )
    (net (code "154") (name "unconnected-(E34A-1Y4-Pad9)") (class "Default")
      (node (ref "E34") (pin "9") (pinfunction "1Y4_9") (pintype "tri_state"))
    )
    (net (code "155") (name "unconnected-(E35A-Y0-Pad15)") (class "Default")
      (node (ref "E35") (pin "15") (pinfunction "Y0_15") (pintype "output"))
    )
    (net (code "156") (name "unconnected-(E35A-Y1-Pad14)") (class "Default")
      (node (ref "E35") (pin "14") (pinfunction "Y1_14") (pintype "output"))
    )
    (net (code "157") (name "unconnected-(E35A-Y2-Pad13)") (class "Default")
      (node (ref "E35") (pin "13") (pinfunction "Y2_13") (pintype "output"))
    )
    (net (code "158") (name "unconnected-(E35A-Y3-Pad12)") (class "Default")
      (node (ref "E35") (pin "12") (pinfunction "Y3_12") (pintype "output"))
    )
    (net (code "159") (name "unconnected-(E35A-Y7-Pad7)") (class "Default")
      (node (ref "E35") (pin "7") (pinfunction "Y7_7") (pintype "output"))
    )
    (net (code "160") (name "unconnected-(E36A-Q3-Pad7)") (class "Default")
      (node (ref "E36") (pin "7") (pinfunction "Q3_7") (pintype "output"))
    )
    (net (code "161") (name "unconnected-(E36A-Q4-Pad10)") (class "Default")
      (node (ref "E36") (pin "10") (pinfunction "Q4_10") (pintype "output"))
    )
    (net (code "162") (name "unconnected-(E36A-Q5-Pad12)") (class "Default")
      (node (ref "E36") (pin "12") (pinfunction "Q5_12") (pintype "output"))
    )
    (net (code "163") (name "~{ADRLTH}") (class "Default")
      (node (ref "E12") (pin "9") (pinfunction "CLK_9") (pintype "input"))
      (node (ref "E14") (pin "9") (pinfunction "CLK_9") (pintype "input"))
      (node (ref "E8") (pin "11") (pinfunction "O_11") (pintype "output"))
    )
    (net (code "164") (name "~{BFSW}") (class "Default")
      (node (ref "E28") (pin "9") (pinfunction "1Y4_9") (pintype "tri_state"))
      (node (ref "J2") (pin "24") (pinfunction "24_24") (pintype "passive"))
    )
    (net (code "165") (name "~{BKDTACNTL}") (class "Default")
      (node (ref "E28") (pin "3") (pinfunction "1Y1_3") (pintype "tri_state"))
      (node (ref "J2") (pin "12") (pinfunction "12_12") (pintype "passive"))
    )
    (net (code "166") (name "~{BOOTF}") (class "Default")
      (node (ref "E16") (pin "2") (pinfunction "D_2") (pintype "input"))
      (node (ref "E16") (pin "6") (pinfunction "~{Q}_6") (pintype "output"))
      (node (ref "E28") (pin "10") (pinfunction "1A4_10") (pintype "input"))
    )
    (net (code "167") (name "~{BUSEN}") (class "Default")
      (node (ref "E34") (pin "13") (pinfunction "2Y2_13") (pintype "tri_state"))
      (node (ref "J1") (pin "24") (pinfunction "24_24") (pintype "passive"))
    )
    (net (code "168") (name "~{DEP}") (class "Default")
      (node (ref "E28") (pin "5") (pinfunction "1Y2_5") (pintype "tri_state"))
      (node (ref "J2") (pin "20") (pinfunction "20_20") (pintype "passive"))
    )
    (net (code "169") (name "~{DSPLTH}") (class "Default")
      (node (ref "E13") (pin "9") (pinfunction "CLK_9") (pintype "input"))
      (node (ref "E15") (pin "9") (pinfunction "CLK_9") (pintype "input"))
      (node (ref "E8") (pin "8") (pinfunction "O_8") (pintype "output"))
    )
    (net (code "170") (name "~{EMA0}") (class "Default")
      (node (ref "E27") (pin "11") (pinfunction "I_11") (pintype "input"))
      (node (ref "J1") (pin "30") (pinfunction "30_30") (pintype "passive"))
      (node (ref "R34") (pin "2") (pinfunction "2_2") (pintype "passive"))
    )
    (net (code "171") (name "~{EMA1}") (class "Default")
      (node (ref "E27") (pin "9") (pinfunction "I_9") (pintype "input"))
      (node (ref "J1") (pin "28") (pinfunction "28_28") (pintype "passive"))
      (node (ref "R35") (pin "2") (pinfunction "2_2") (pintype "passive"))
    )
    (net (code "172") (name "~{EMA2}") (class "Default")
      (node (ref "E27") (pin "13") (pinfunction "I_13") (pintype "input"))
      (node (ref "J1") (pin "32") (pinfunction "32_32") (pintype "passive"))
      (node (ref "R36") (pin "2") (pinfunction "2_2") (pintype "passive"))
    )
    (net (code "173") (name "~{EMODE}") (class "Default")
      (node (ref "E1") (pin "6") (pinfunction "MOD_6") (pintype "input"))
      (node (ref "E16") (pin "8") (pinfunction "~{Q}_8") (pintype "output"))
      (node (ref "E2") (pin "6") (pinfunction "MOD_6") (pintype "input"))
      (node (ref "E22") (pin "6") (pinfunction "I1_6") (pintype "input"))
      (node (ref "E3") (pin "6") (pinfunction "MOD_6") (pintype "input"))
    )
    (net (code "174") (name "~{EXTPUL}") (class "Default")
      (node (ref "J4") (pin "9") (pinfunction "9_9") (pintype "passive"))
    )
    (net (code "175") (name "~{FUN}") (class "Default")
      (node (ref "E24") (pin "3") (pinfunction "I_3") (pintype "input"))
      (node (ref "E25") (pin "11") (pinfunction "I2_11") (pintype "input"))
      (node (ref "E25") (pin "2") (pinfunction "I1_2") (pintype "input"))
      (node (ref "J4") (pin "15") (pinfunction "15_15") (pintype "passive"))
    )
    (net (code "176") (name "~{GATEENT}") (class "Default")
      (node (ref "E10") (pin "1") (pinfunction "G_1") (pintype "input"))
      (node (ref "E11") (pin "1") (pinfunction "G_1") (pintype "input"))
      (node (ref "E21") (pin "6") (pinfunction "O_6") (pintype "output"))
      (node (ref "E30") (pin "5") (pinfunction "I1_5") (pintype "input"))
      (node (ref "E9") (pin "1") (pinfunction "G_1") (pintype "input"))
    )
    (net (code "177") (name "~{GATESR}") (class "Default")
      (node (ref "E10") (pin "19") (pinfunction "G_19") (pintype "input"))
      (node (ref "E11") (pin "19") (pinfunction "G_19") (pintype "input"))
      (node (ref "E32") (pin "11") (pinfunction "O_11") (pintype "output"))
      (node (ref "E9") (pin "19") (pinfunction "G_19") (pintype "input"))
    )
    (net (code "178") (name "~{IND1}") (class "Default")
      (node (ref "E28") (pin "7") (pinfunction "1Y3_7") (pintype "tri_state"))
      (node (ref "E34") (pin "3") (pinfunction "1Y1_3") (pintype "tri_state"))
      (node (ref "J2") (pin "8") (pinfunction "8_8") (pintype "passive"))
    )
    (net (code "179") (name "~{IND2}") (class "Default")
      (node (ref "E34") (pin "5") (pinfunction "1Y2_5") (pintype "tri_state"))
      (node (ref "J2") (pin "4") (pinfunction "4_4") (pintype "passive"))
    )
    (net (code "180") (name "~{INIT}") (class "Default")
      (node (ref "E31") (pin "9") (pinfunction "1Y4_9") (pintype "tri_state"))
      (node (ref "J2") (pin "34") (pinfunction "34_34") (pintype "passive"))
    )
    (net (code "181") (name "~{KEY-F}") (class "Default")
      (node (ref "E26") (pin "13") (pinfunction "C12_13") (pintype "input"))
      (node (ref "E26") (pin "4") (pinfunction "C34_4") (pintype "input"))
      (node (ref "E27") (pin "5") (pinfunction "I_5") (pintype "input"))
      (node (ref "J4") (pin "3") (pinfunction "3_3") (pintype "passive"))
    )
    (net (code "182") (name "~{KEYCNTL}") (class "Default")
      (node (ref "E31") (pin "13") (pinfunction "2Y2_13") (pintype "tri_state"))
      (node (ref "J2") (pin "10") (pinfunction "10_10") (pintype "passive"))
    )
    (net (code "183") (name "~{KEYSTB}") (class "Default")
      (node (ref "E16") (pin "11") (pinfunction "CLK_11") (pintype "input"))
      (node (ref "E21") (pin "2") (pinfunction "I1_2") (pintype "input"))
      (node (ref "E24") (pin "2") (pinfunction "O_2") (pintype "output"))
      (node (ref "E31") (pin "1") (pinfunction "1G_1") (pintype "input"))
      (node (ref "E33") (pin "11") (pinfunction "I0_11") (pintype "input"))
      (node (ref "E33") (pin "9") (pinfunction "I1_9") (pintype "input"))
    )
    (net (code "184") (name "~{KFUN0}") (class "Default")
      (node (ref "E26") (pin "2") (pinfunction "D1_2") (pintype "input"))
      (node (ref "E3") (pin "1") (pinfunction "SER_1") (pintype "input"))
      (node (ref "E3") (pin "2") (pinfunction "A_2") (pintype "input"))
      (node (ref "J3") (pin "3") (pinfunction "3_3") (pintype "passive"))
    )
    (net (code "185") (name "~{KFUN1}") (class "Default")
      (node (ref "E2") (pin "1") (pinfunction "SER_1") (pintype "input"))
      (node (ref "E2") (pin "2") (pinfunction "A_2") (pintype "input"))
      (node (ref "E26") (pin "3") (pinfunction "D2_3") (pintype "input"))
      (node (ref "J3") (pin "2") (pinfunction "2_2") (pintype "passive"))
    )
    (net (code "186") (name "~{KFUN2}") (class "Default")
      (node (ref "E1") (pin "1") (pinfunction "SER_1") (pintype "input"))
      (node (ref "E1") (pin "2") (pinfunction "A_2") (pintype "input"))
      (node (ref "E26") (pin "6") (pinfunction "D3_6") (pintype "input"))
      (node (ref "J3") (pin "1") (pinfunction "1_1") (pintype "passive"))
    )
    (net (code "187") (name "~{LAENAB}") (class "Default")
      (node (ref "E23") (pin "2") (pinfunction "O_2") (pintype "open_collector"))
      (node (ref "J2") (pin "22") (pinfunction "22_22") (pintype "passive"))
    )
    (net (code "188") (name "~{MAEN}") (class "Default")
      (node (ref "E23") (pin "8") (pinfunction "O_8") (pintype "open_collector"))
      (node (ref "J2") (pin "32") (pinfunction "32_32") (pintype "passive"))
    )
    (net (code "189") (name "~{MALC}") (class "Default")
      (node (ref "E28") (pin "11") (pinfunction "2Y1_11") (pintype "tri_state"))
      (node (ref "J2") (pin "36") (pinfunction "36_36") (pintype "passive"))
    )
    (net (code "190") (name "~{MCLOCK}") (class "Default")
      (node (ref "E33") (pin "2") (pinfunction "I0_2") (pintype "input"))
      (node (ref "J4") (pin "1") (pinfunction "1_1") (pintype "passive"))
    )
    (net (code "191") (name "~{MD}") (class "Default")
      (node (ref "E34") (pin "7") (pinfunction "1Y3_7") (pintype "tri_state"))
      (node (ref "J2") (pin "18") (pinfunction "18_18") (pintype "passive"))
    )
    (net (code "192") (name "~{MEMSTART}") (class "Default")
      (node (ref "E23") (pin "12") (pinfunction "O_12") (pintype "open_collector"))
      (node (ref "J2") (pin "26") (pinfunction "26_26") (pintype "passive"))
    )
    (net (code "193") (name "~{MH0}") (class "Default")
      (node (ref "E20") (pin "12") (pinfunction "D_12") (pintype "input"))
      (node (ref "E20") (pin "8") (pinfunction "~{Q}_8") (pintype "output"))
      (node (ref "E21") (pin "9") (pinfunction "I0_9") (pintype "input"))
      (node (ref "E8") (pin "2") (pinfunction "I1_2") (pintype "input"))
      (node (ref "E8") (pin "9") (pinfunction "I0_9") (pintype "input"))
    )
    (net (code "194") (name "~{MSIRDIS}") (class "Default")
      (node (ref "E31") (pin "11") (pinfunction "2Y1_11") (pintype "tri_state"))
      (node (ref "J2") (pin "2") (pinfunction "2_2") (pintype "passive"))
    )
    (net (code "195") (name "~{PANLOCK}") (class "Default")
      (node (ref "E24") (pin "13") (pinfunction "I_13") (pintype "input"))
      (node (ref "J2") (pin "6") (pinfunction "6_6") (pintype "passive"))
      (node (ref "R31") (pin "1") (pinfunction "1_1") (pintype "passive"))
    )
    (net (code "196") (name "~{PULSELOADADD}") (class "Default")
      (node (ref "E31") (pin "7") (pinfunction "1Y3_7") (pintype "tri_state"))
      (node (ref "J2") (pin "40") (pinfunction "40_40") (pintype "passive"))
    )
    (net (code "197") (name "~{RUN}") (class "Default")
      (node (ref "E24") (pin "5") (pinfunction "I_5") (pintype "input"))
      (node (ref "J1") (pin "18") (pinfunction "18_18") (pintype "passive"))
      (node (ref "R28") (pin "1") (pinfunction "1_1") (pintype "passive"))
    )
    (net (code "198") (name "~{SHLT}") (class "Default")
      (node (ref "E27") (pin "1") (pinfunction "I_1") (pintype "input"))
      (node (ref "J3") (pin "5") (pinfunction "5_5") (pintype "passive"))
    )
    (net (code "199") (name "~{SINGSTEP}") (class "Default")
      (node (ref "E28") (pin "13") (pinfunction "2Y2_13") (pintype "tri_state"))
      (node (ref "J2") (pin "14") (pinfunction "14_14") (pintype "passive"))
    )
    (net (code "200") (name "~{SRDATA}") (class "Default")
      (node (ref "E32") (pin "13") (pinfunction "I1_13") (pintype "input"))
      (node (ref "E8") (pin "1") (pinfunction "I0_1") (pintype "input"))
      (node (ref "J2") (pin "30") (pinfunction "30_30") (pintype "passive"))
      (node (ref "R29") (pin "1") (pinfunction "1_1") (pintype "passive"))
      (node (ref "R30") (pin "2") (pinfunction "2_2") (pintype "passive"))
    )
    (net (code "201") (name "~{STATE}") (class "Default")
      (node (ref "E34") (pin "11") (pinfunction "2Y1_11") (pintype "tri_state"))
      (node (ref "J2") (pin "38") (pinfunction "38_38") (pintype "passive"))
    )
    (net (code "202") (name "~{STHIS}") (class "Default")
      (node (ref "E20") (pin "2") (pinfunction "D_2") (pintype "input"))
      (node (ref "J3") (pin "4") (pinfunction "4_4") (pintype "passive"))
    )
    (net (code "203") (name "~{TS1}") (class "Default")
      (node (ref "E20") (pin "3") (pinfunction "CLK_3") (pintype "input"))
      (node (ref "E21") (pin "10") (pinfunction "I1_10") (pintype "input"))
      (node (ref "E24") (pin "9") (pinfunction "I_9") (pintype "input"))
      (node (ref "J1") (pin "26") (pinfunction "26_26") (pintype "passive"))
      (node (ref "R26") (pin "1") (pinfunction "1_1") (pintype "passive"))
      (node (ref "R27") (pin "2") (pinfunction "2_2") (pintype "passive"))
    )
  )
)
